# CrowPanel_Pico_Display-3_5_V1_0-240412.net
KiCad netlist of a schematic drawn in EAGLE
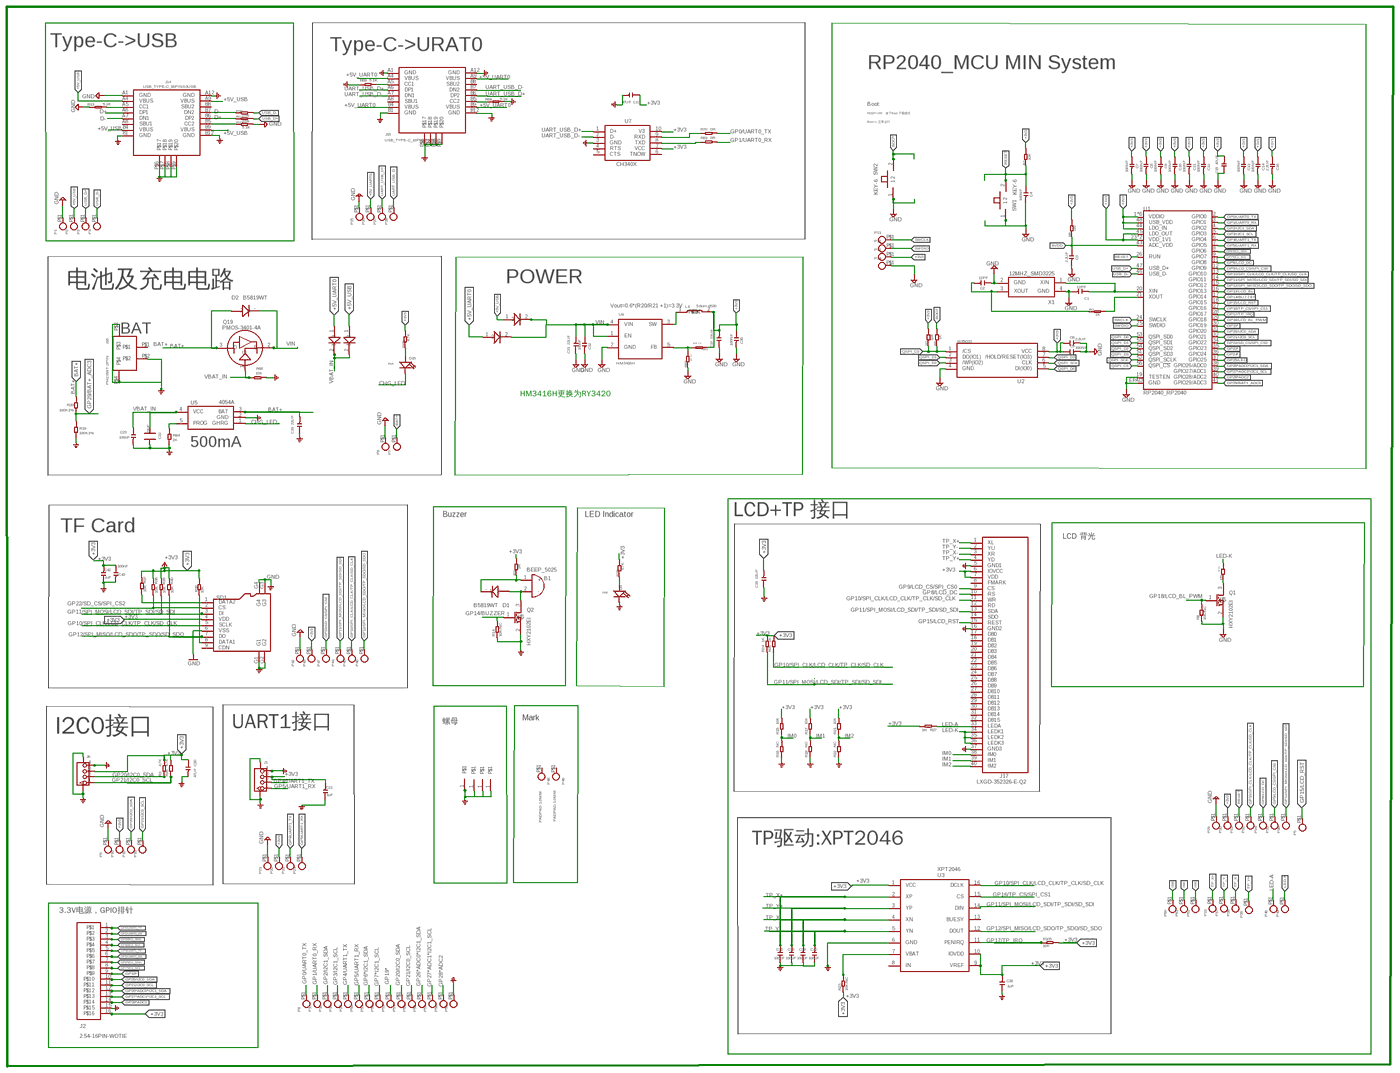
[diagram p0: schematic, sheet 1, overview]
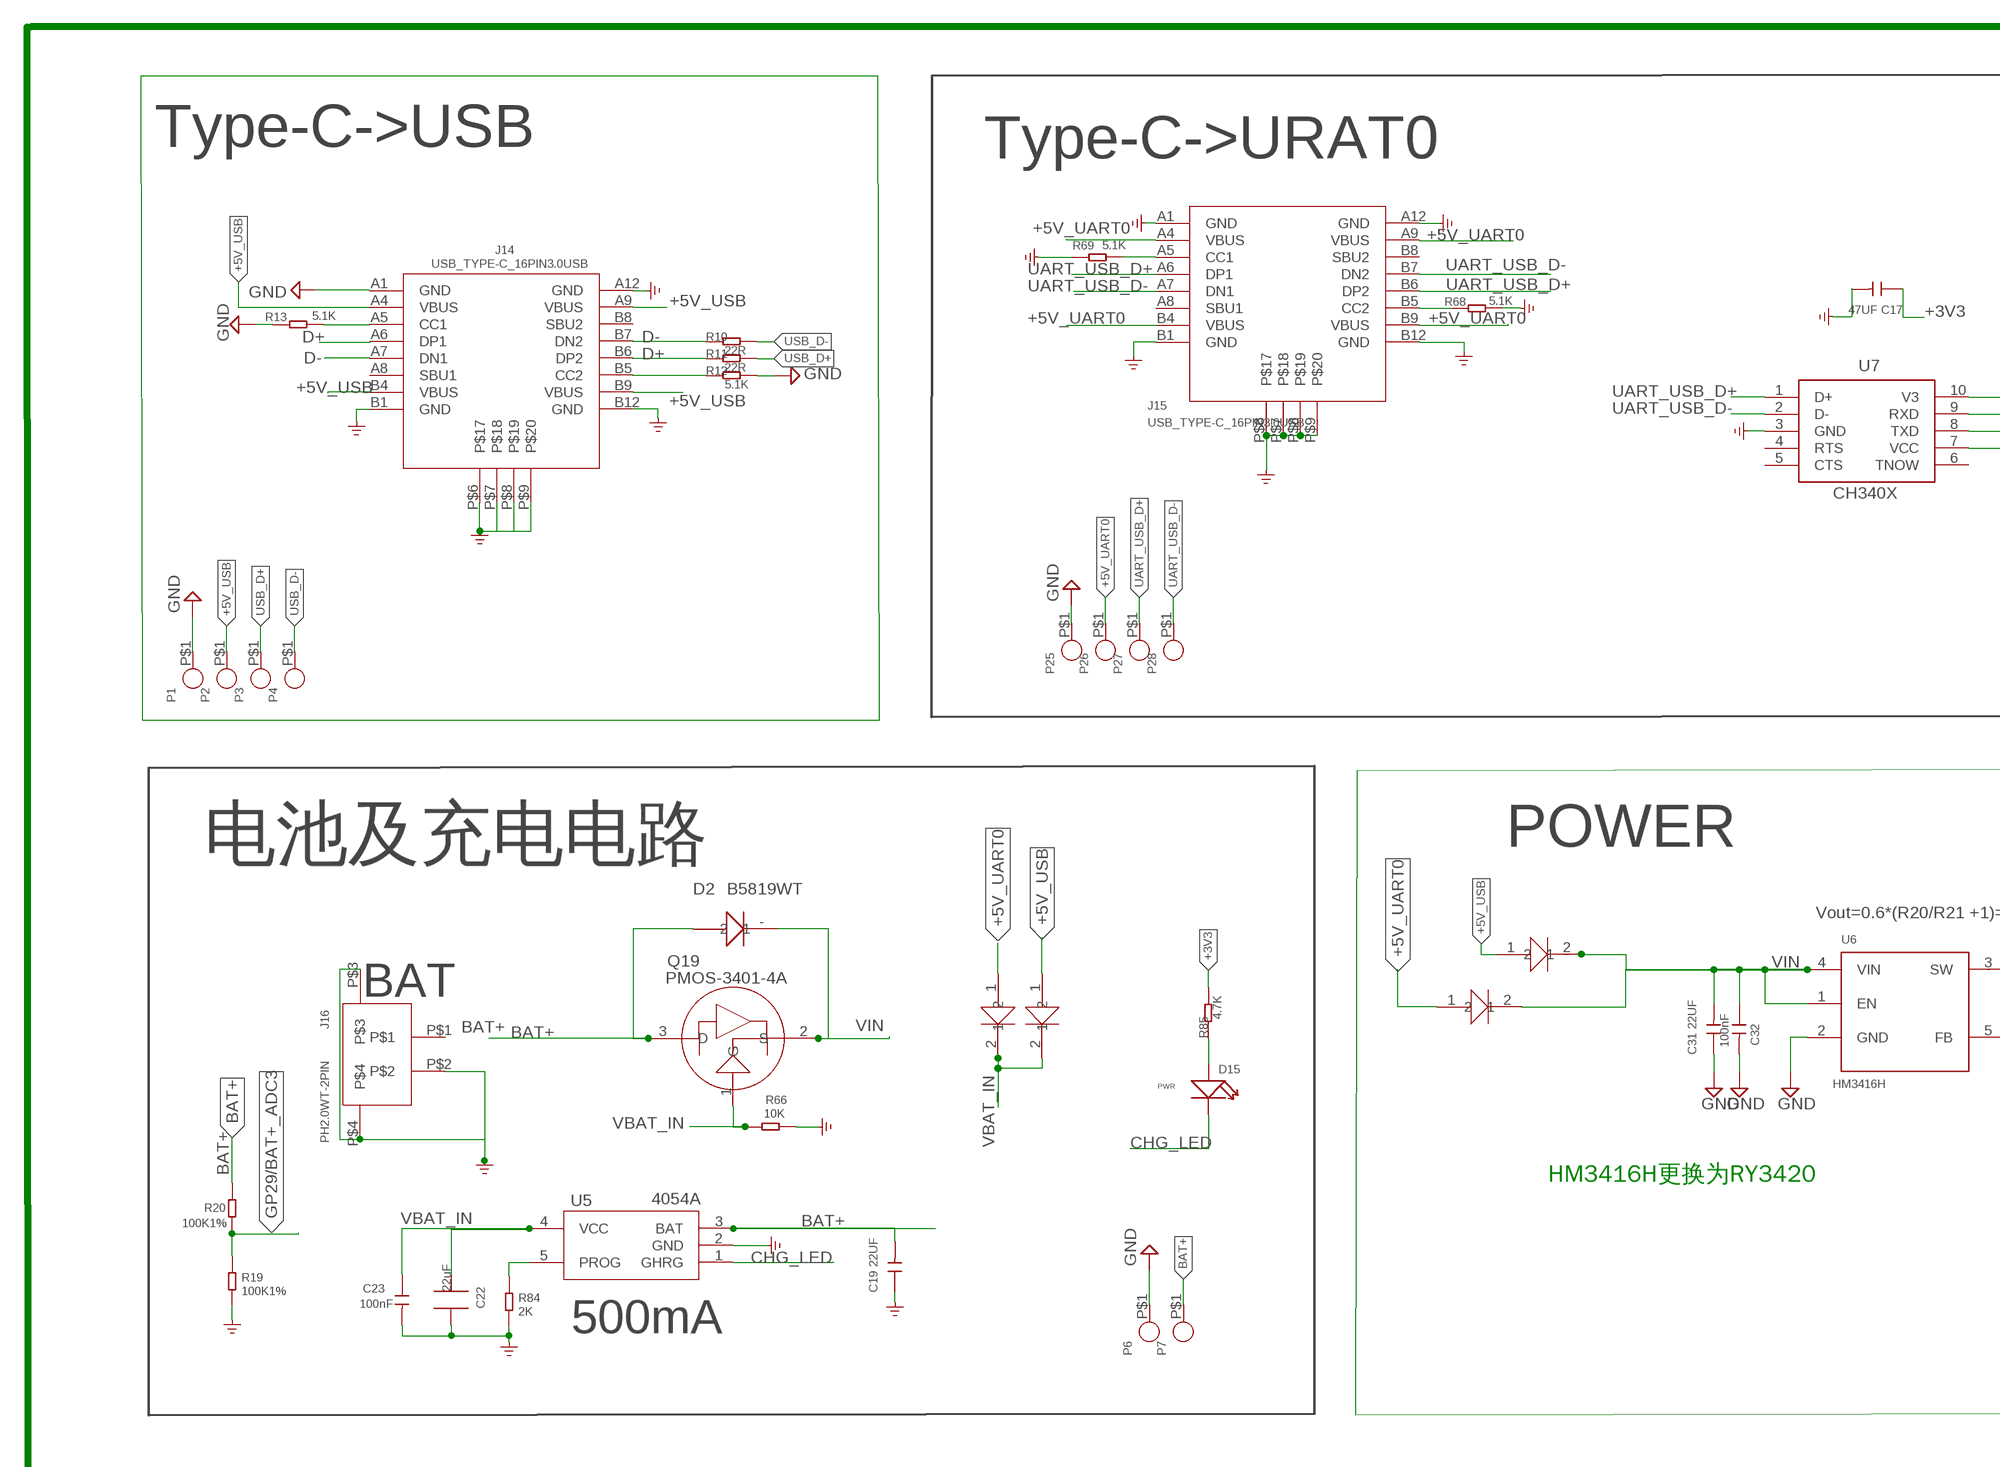
[diagram p1: schematic, sheet 1, part 1 of 4]
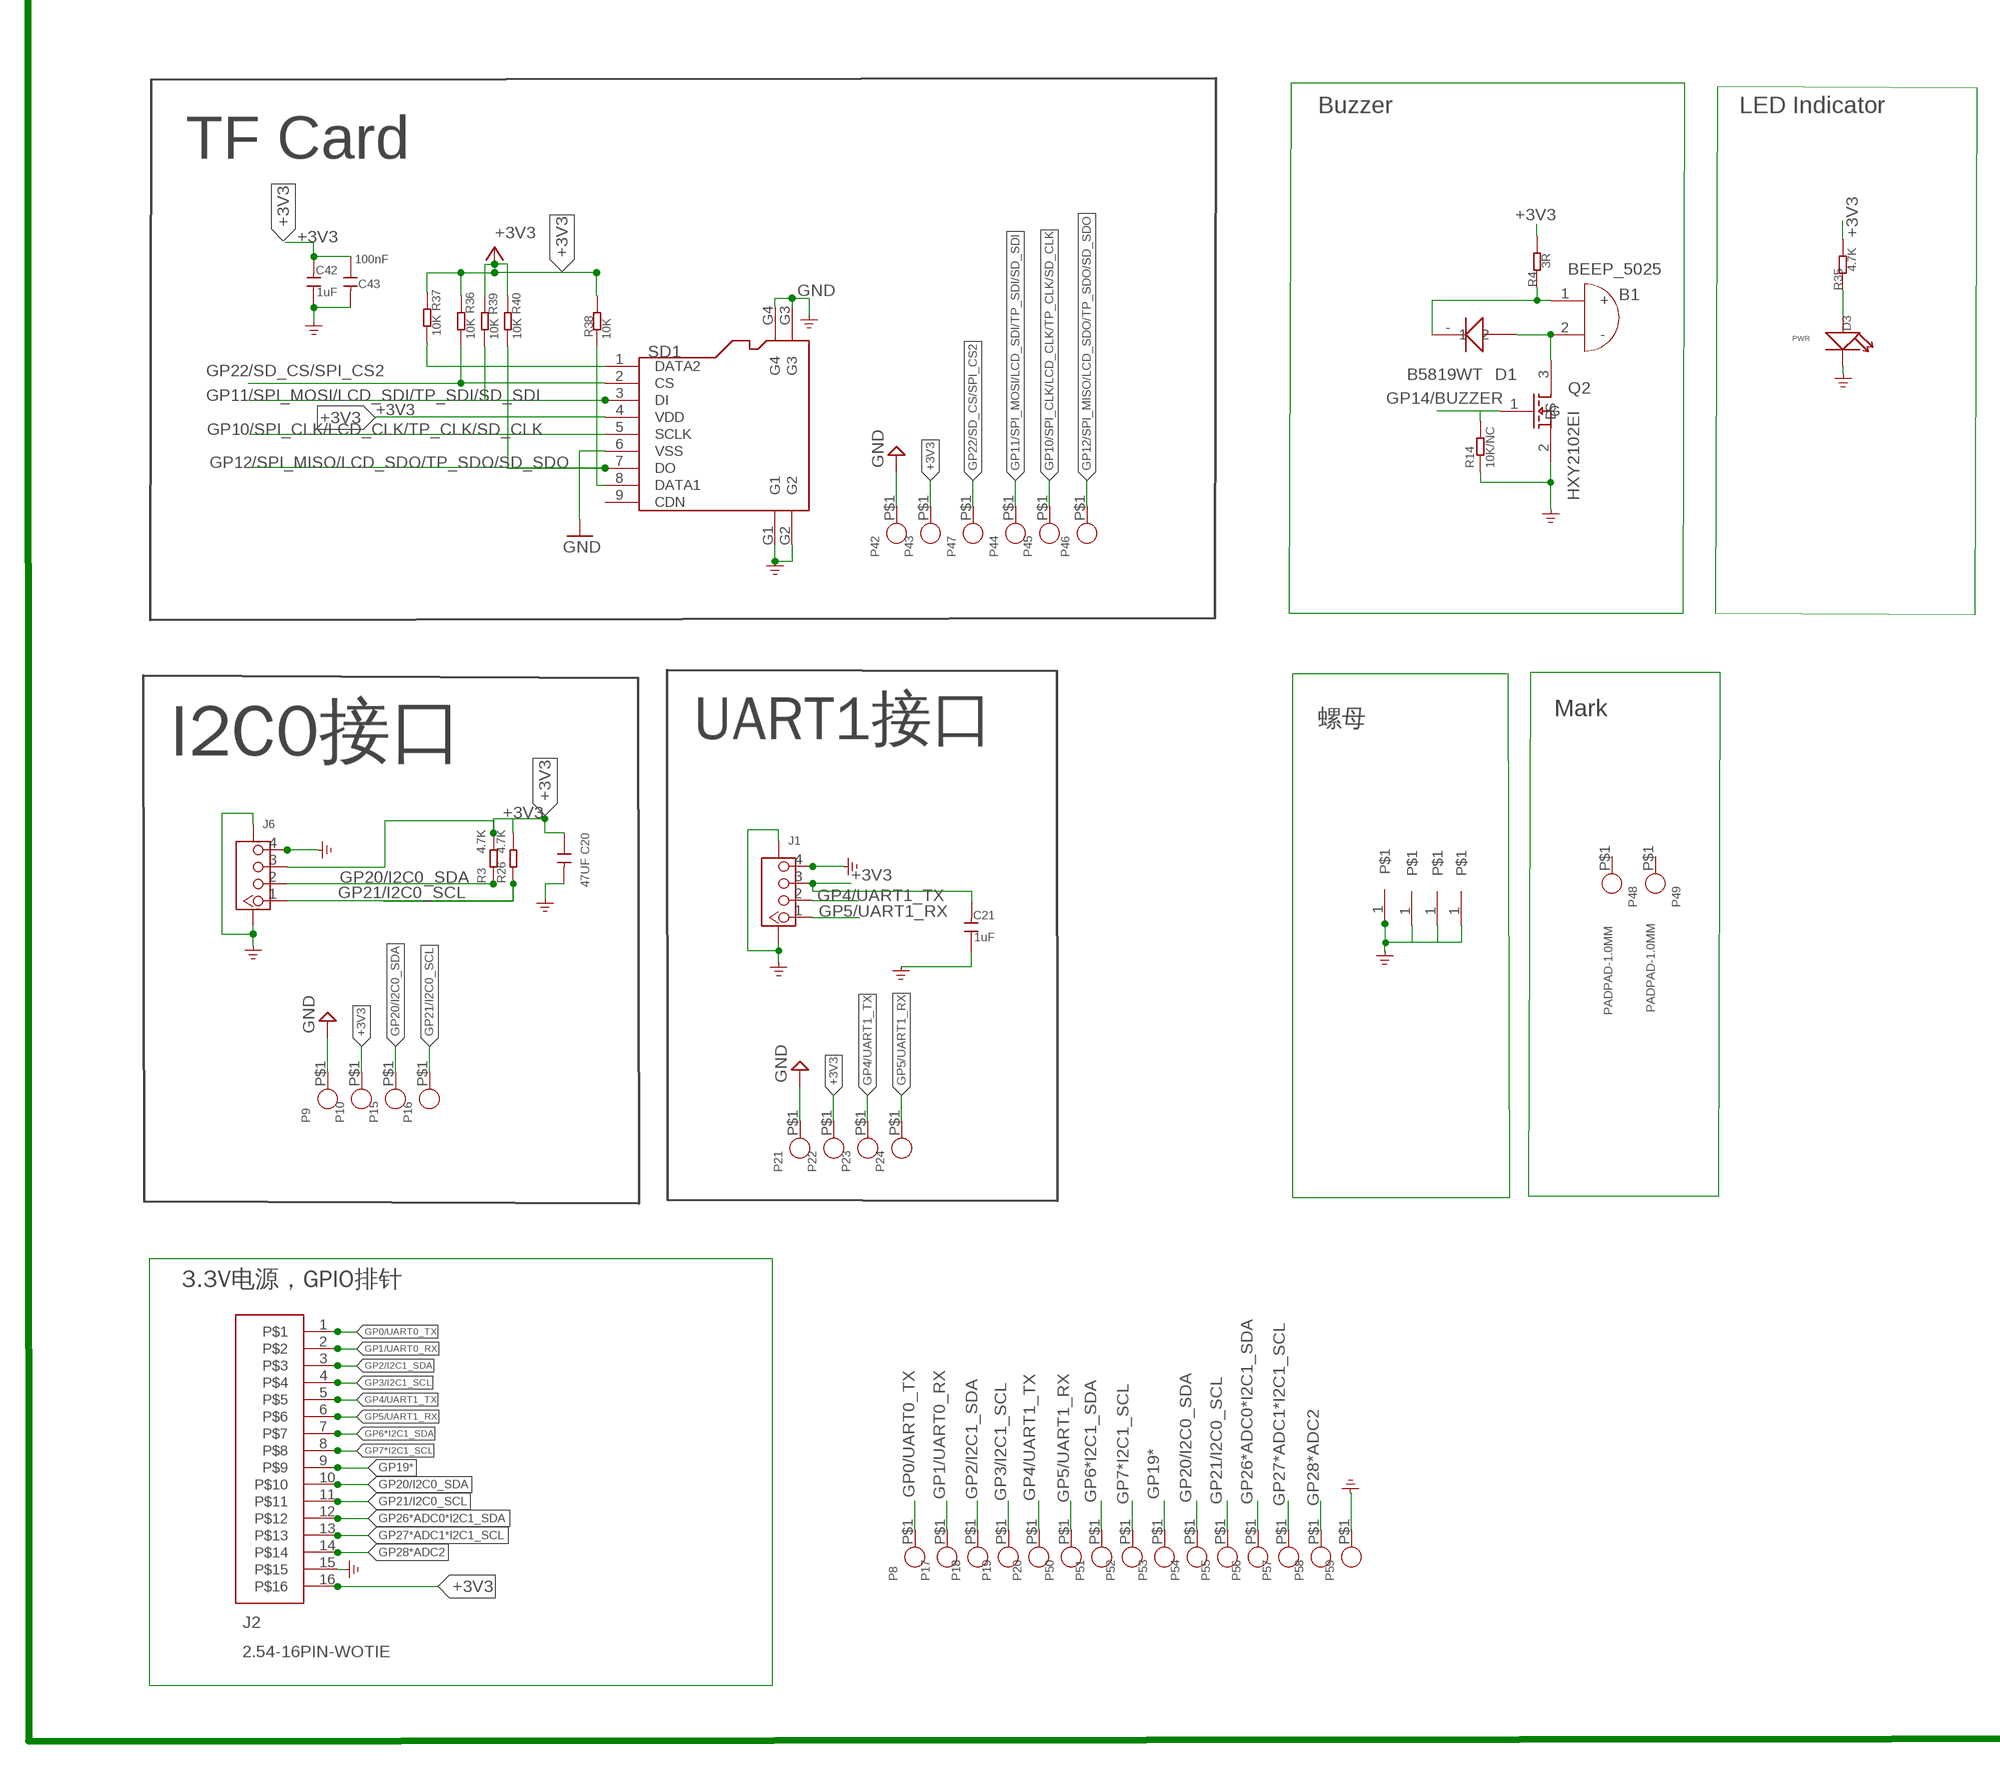
[diagram p2: schematic, sheet 1, part 2 of 4]
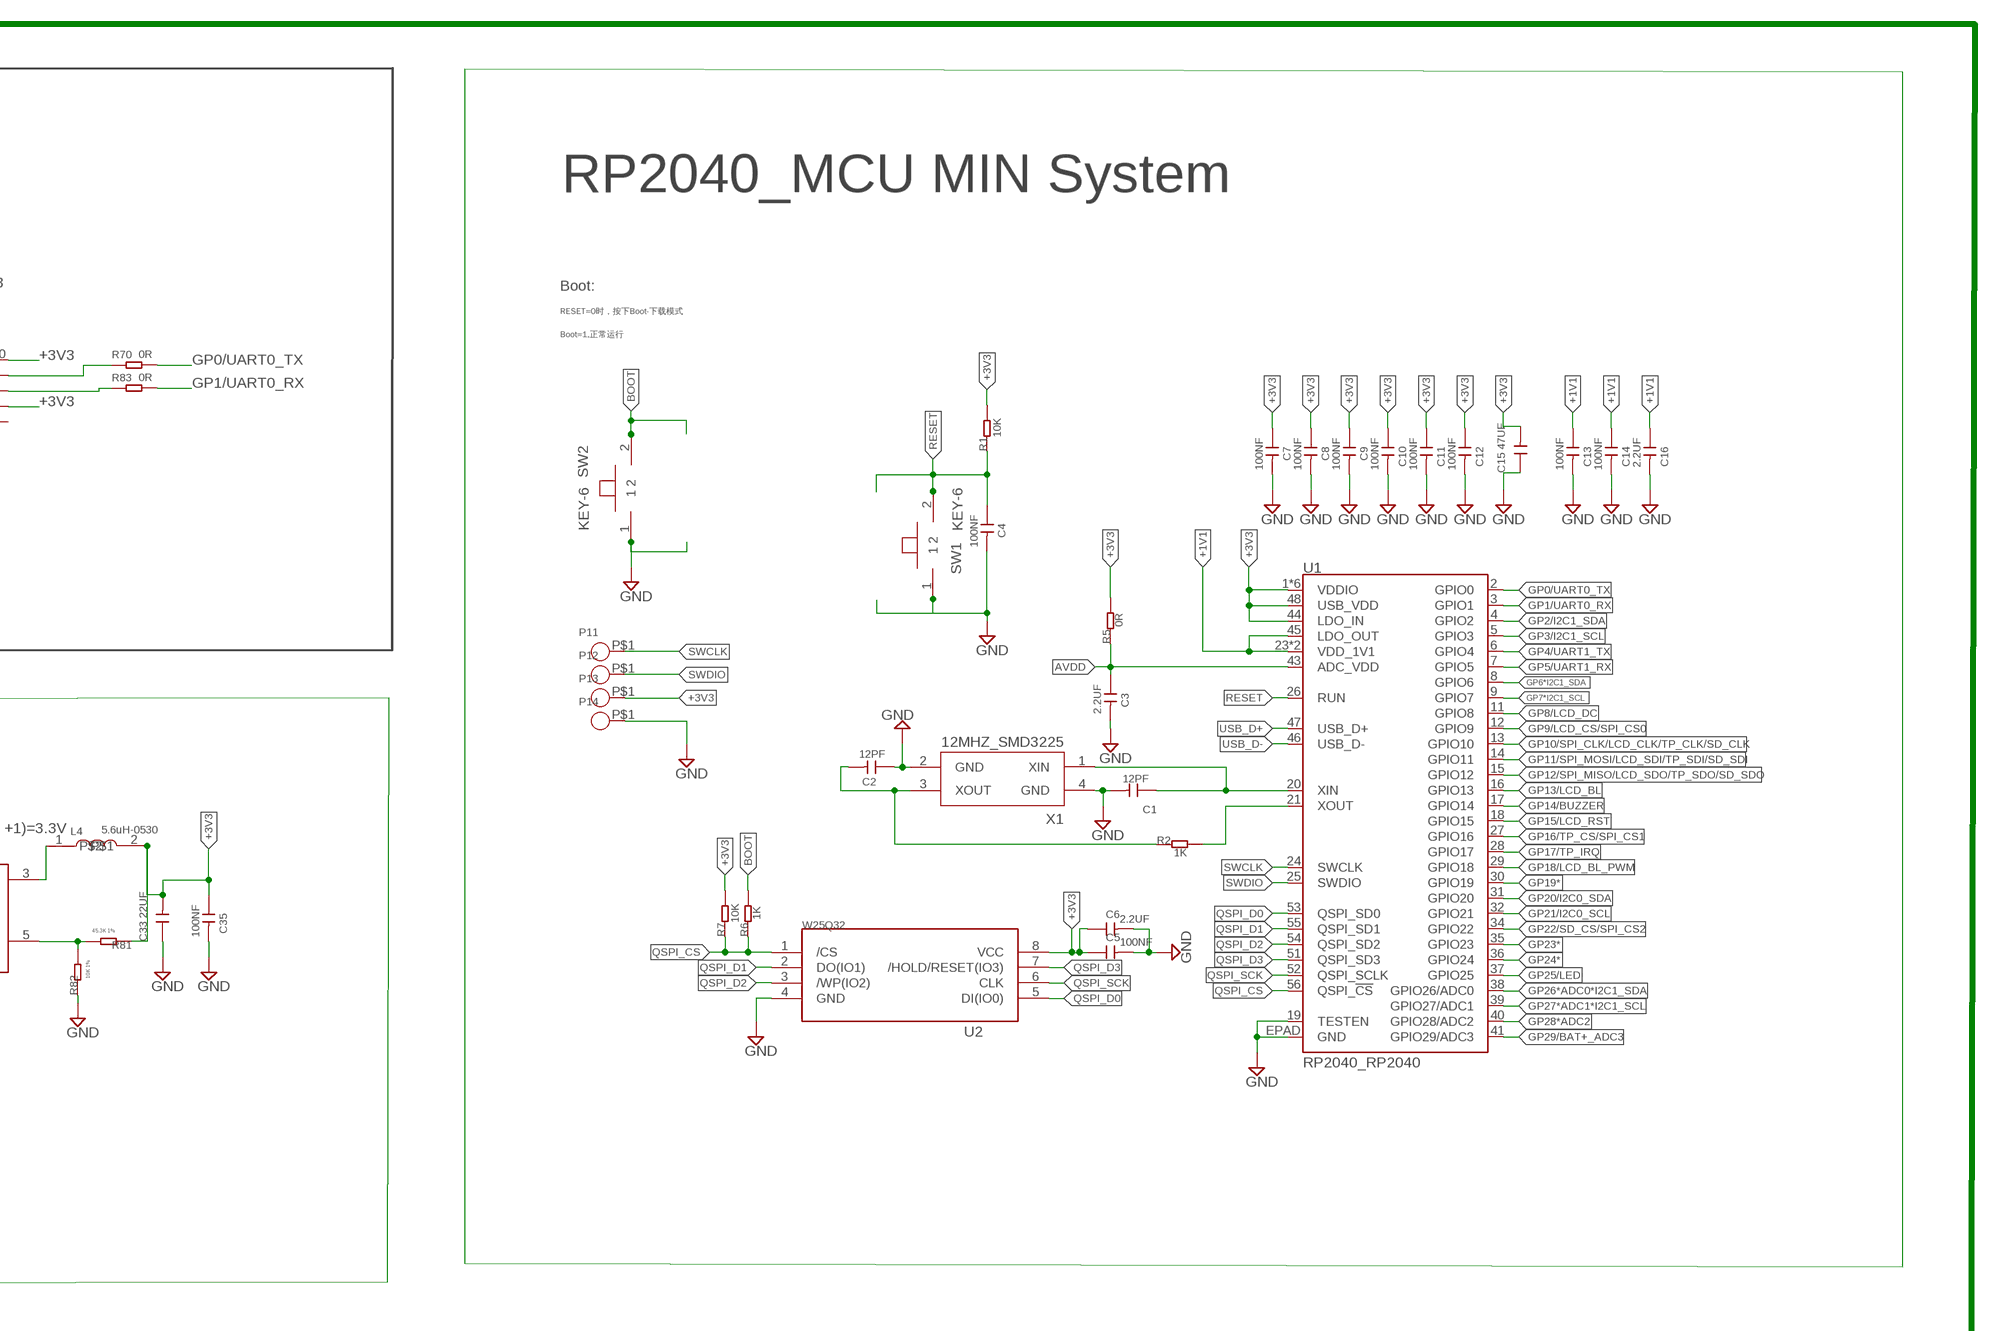
[diagram p3: schematic, sheet 1, part 3 of 4]
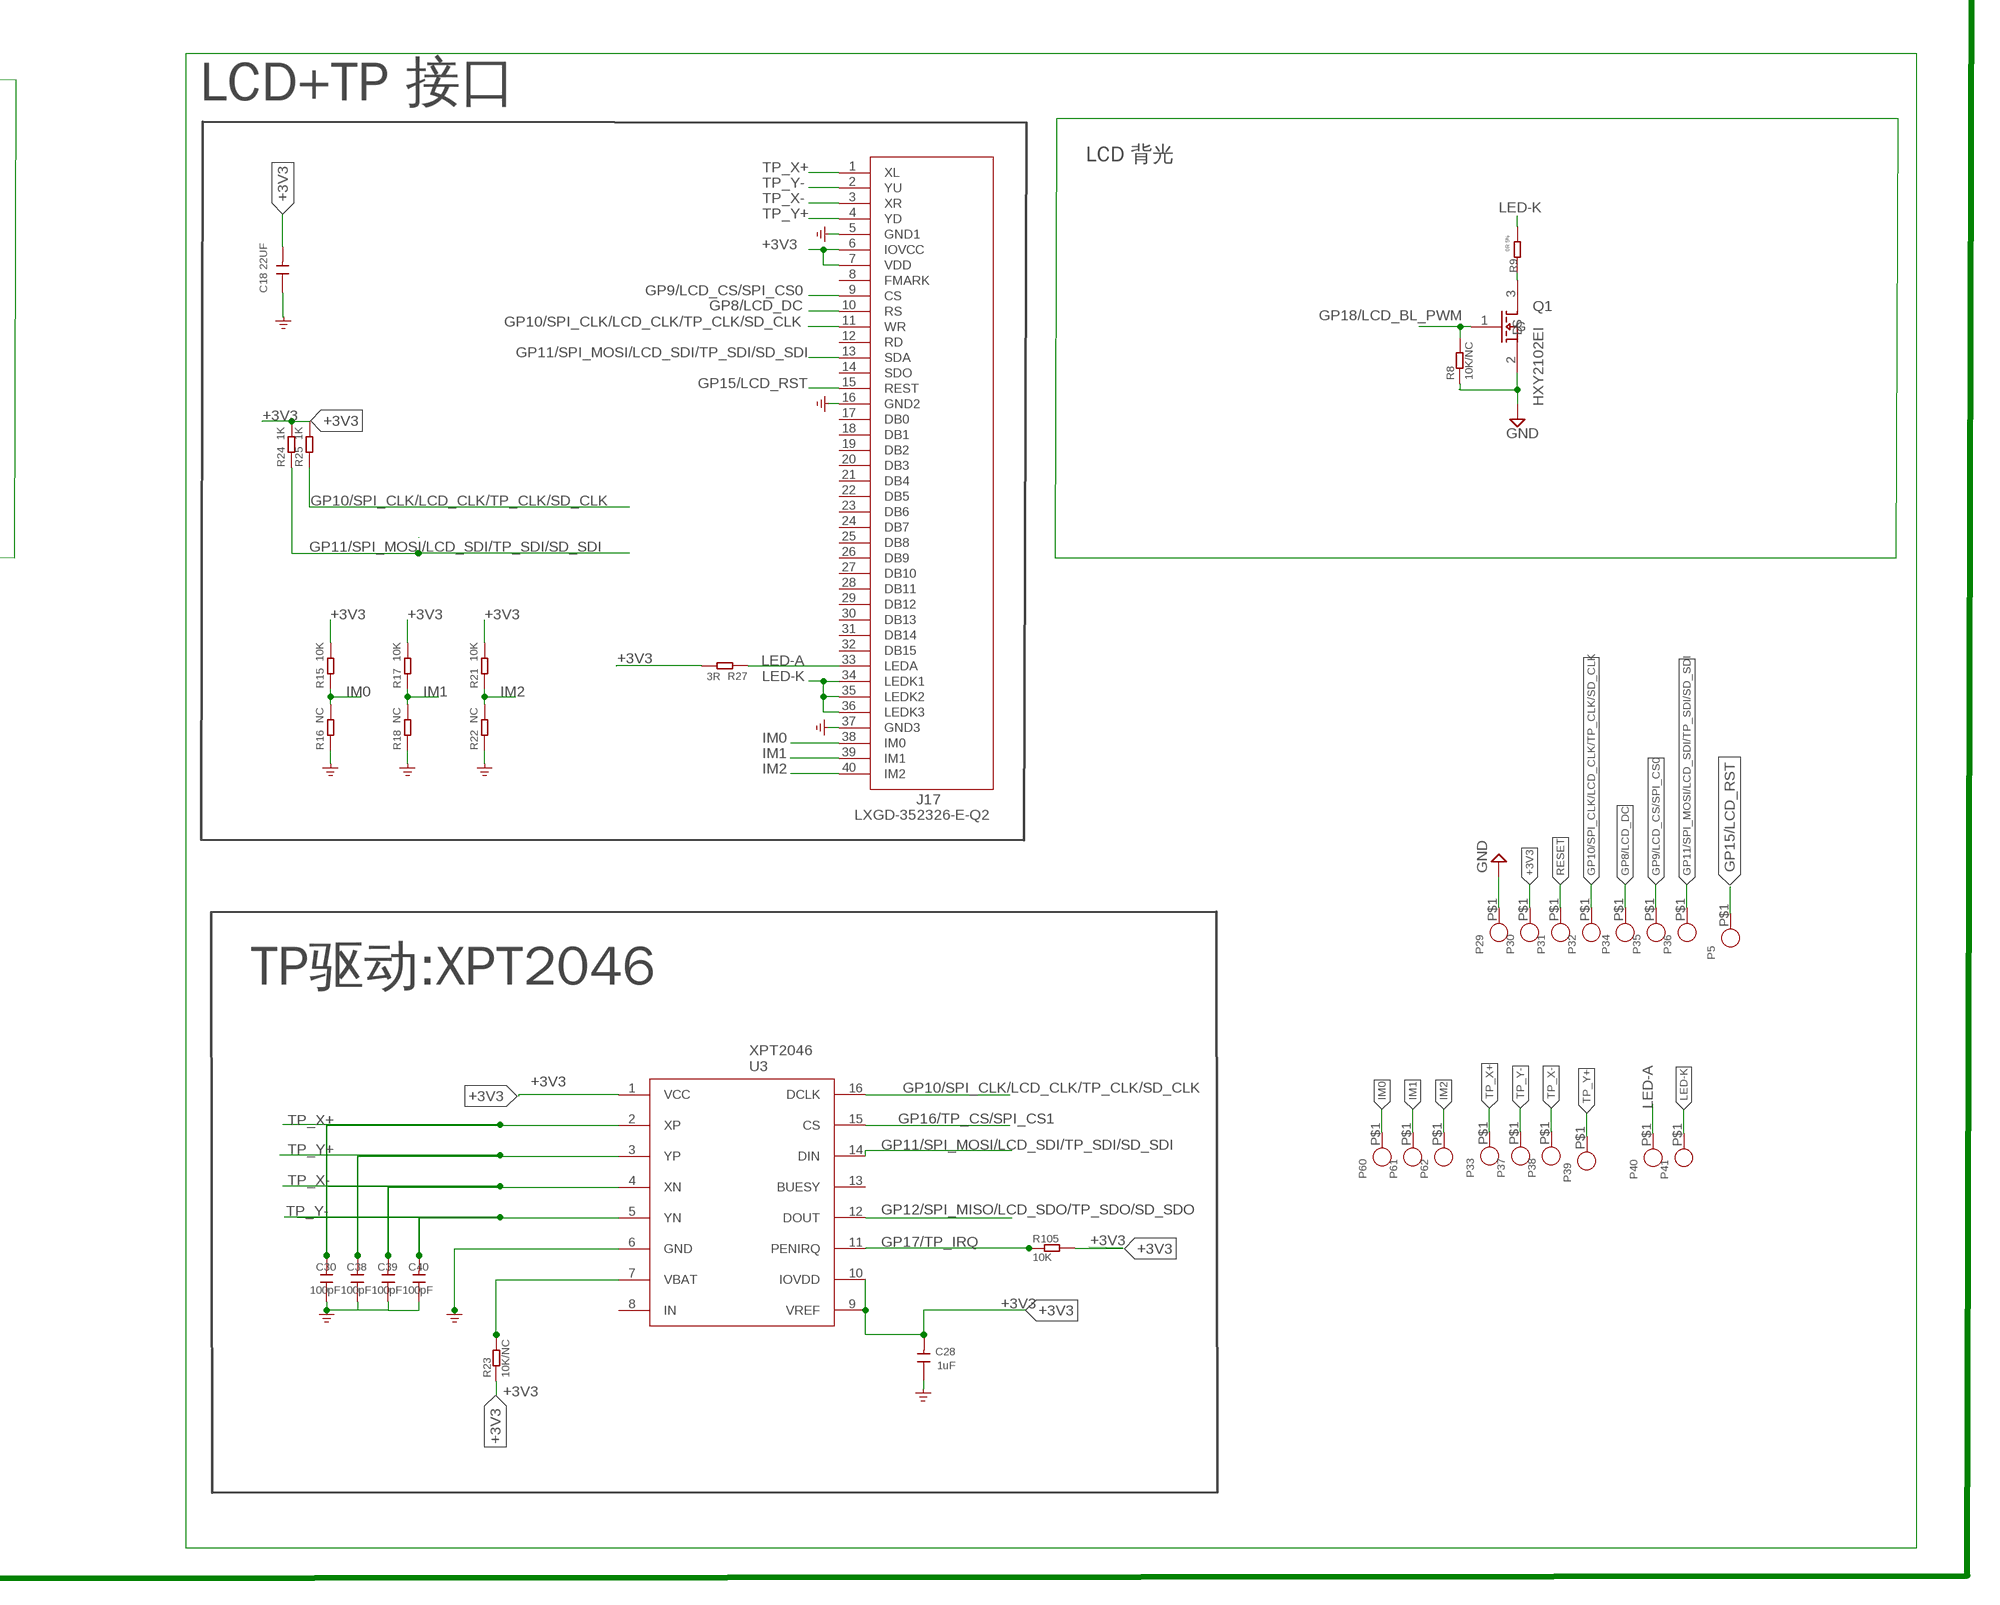
[diagram p4: schematic, sheet 1, part 4 of 4]

(export (version "E")
  (design (tool "Eeschema 10.0.6"))
  (components
    (comp (ref "B1")
      (value "BEEP_5025")
      (footprint "eagle-import:BEEP_5025")
      (libsource (lib "eagle-import") (part "BEEP_5025"))
    )
    (comp (ref "C1")
      (value "12PF")
      (footprint "eagle-import:A_XBJ_0603")
      (libsource (lib "eagle-import") (part "A_XBJ_C0603"))
    )
    (comp (ref "C2")
      (value "12PF")
      (footprint "eagle-import:A_XBJ_0603")
      (libsource (lib "eagle-import") (part "A_XBJ_C0603"))
    )
    (comp (ref "C3")
      (value "2.2UF")
      (footprint "eagle-import:A_XBJ_0603")
      (libsource (lib "eagle-import") (part "A_XBJ_C0603"))
    )
    (comp (ref "C4")
      (value "100NF")
      (footprint "eagle-import:A_XBJ_0603")
      (libsource (lib "eagle-import") (part "A_XBJ_C0603"))
    )
    (comp (ref "C5")
      (value "100NF")
      (footprint "eagle-import:A_XBJ_0603")
      (libsource (lib "eagle-import") (part "A_XBJ_C0603"))
    )
    (comp (ref "C6")
      (value "2.2UF")
      (footprint "eagle-import:A_XBJ_0603")
      (libsource (lib "eagle-import") (part "A_XBJ_C0603"))
    )
    (comp (ref "C7")
      (value "100NF")
      (footprint "eagle-import:A_XBJ_0603")
      (libsource (lib "eagle-import") (part "A_XBJ_C0603"))
    )
    (comp (ref "C8")
      (value "100NF")
      (footprint "eagle-import:A_XBJ_0603")
      (libsource (lib "eagle-import") (part "A_XBJ_C0603"))
    )
    (comp (ref "C9")
      (value "100NF")
      (footprint "eagle-import:A_XBJ_0603")
      (libsource (lib "eagle-import") (part "A_XBJ_C0603"))
    )
    (comp (ref "C10")
      (value "100NF")
      (footprint "eagle-import:A_XBJ_0603")
      (libsource (lib "eagle-import") (part "A_XBJ_C0603"))
    )
    (comp (ref "C11")
      (value "100NF")
      (footprint "eagle-import:A_XBJ_0603")
      (libsource (lib "eagle-import") (part "A_XBJ_C0603"))
    )
    (comp (ref "C12")
      (value "100NF")
      (footprint "eagle-import:A_XBJ_0603")
      (libsource (lib "eagle-import") (part "A_XBJ_C0603"))
    )
    (comp (ref "C13")
      (value "100NF")
      (footprint "eagle-import:A_XBJ_0603")
      (libsource (lib "eagle-import") (part "A_XBJ_C0603"))
    )
    (comp (ref "C14")
      (value "100NF")
      (footprint "eagle-import:A_XBJ_0603")
      (libsource (lib "eagle-import") (part "A_XBJ_C0603"))
    )
    (comp (ref "C15")
      (value "47UF")
      (footprint "eagle-import:A_XBJ_0805")
      (libsource (lib "eagle-import") (part "A_XBJ_C0805"))
    )
    (comp (ref "C16")
      (value "2.2UF")
      (footprint "eagle-import:A_XBJ_0603")
      (libsource (lib "eagle-import") (part "A_XBJ_C0603"))
    )
    (comp (ref "C17")
      (value "47UF")
      (footprint "eagle-import:A_XBJ_0805")
      (libsource (lib "eagle-import") (part "A_XBJ_C0805"))
    )
    (comp (ref "C18")
      (value "22UF")
      (footprint "eagle-import:A_XBJ_0805")
      (libsource (lib "eagle-import") (part "A_XBJ_C0805"))
    )
    (comp (ref "C19")
      (value "22UF")
      (footprint "eagle-import:A_XBJ_0805")
      (libsource (lib "eagle-import") (part "A_XBJ_C0805"))
    )
    (comp (ref "C20")
      (value "47UF")
      (footprint "eagle-import:A_XBJ_0805")
      (libsource (lib "eagle-import") (part "A_XBJ_C0805"))
    )
    (comp (ref "C21")
      (value "1uF")
      (footprint "eagle-import:DISCRETE_C0603")
      (libsource (lib "eagle-import") (part "DISCRETE_C-0603"))
    )
    (comp (ref "C22")
      (value "22uF")
      (footprint "eagle-import:0805_S")
      (libsource (lib "eagle-import") (part "C0805_S"))
    )
    (comp (ref "C23")
      (value "100nF")
      (footprint "eagle-import:C0603")
      (libsource (lib "eagle-import") (part "C-0603"))
    )
    (comp (ref "C28")
      (value "1uF")
      (footprint "eagle-import:DISCRETE_C0603")
      (libsource (lib "eagle-import") (part "DISCRETE_C-0603"))
    )
    (comp (ref "C30")
      (value "100pF")
      (footprint "eagle-import:0603")
      (libsource (lib "eagle-import") (part "C0603"))
    )
    (comp (ref "C31")
      (value "22UF")
      (footprint "eagle-import:A_XBJ_0805")
      (libsource (lib "eagle-import") (part "A_XBJ_C0805"))
    )
    (comp (ref "C32")
      (value "100nF")
      (footprint "eagle-import:A_XBJ_0603")
      (libsource (lib "eagle-import") (part "A_XBJ_C0603"))
    )
    (comp (ref "C33")
      (value "22UF")
      (footprint "eagle-import:A_XBJ_0805")
      (libsource (lib "eagle-import") (part "A_XBJ_C0805"))
    )
    (comp (ref "C35")
      (value "100NF")
      (footprint "eagle-import:A_XBJ_0603")
      (libsource (lib "eagle-import") (part "A_XBJ_C0603"))
    )
    (comp (ref "C38")
      (value "100pF")
      (footprint "eagle-import:0603")
      (libsource (lib "eagle-import") (part "C0603"))
    )
    (comp (ref "C39")
      (value "100pF")
      (footprint "eagle-import:0603")
      (libsource (lib "eagle-import") (part "C0603"))
    )
    (comp (ref "C40")
      (value "100pF")
      (footprint "eagle-import:0603")
      (libsource (lib "eagle-import") (part "C0603"))
    )
    (comp (ref "C42")
      (value "1uF")
      (footprint "eagle-import:DISCRETE_C0603")
      (libsource (lib "eagle-import") (part "DISCRETE_C-0603"))
    )
    (comp (ref "C43")
      (value "100nF")
      (footprint "eagle-import:C0603")
      (libsource (lib "eagle-import") (part "C-0603"))
    )
    (comp (ref "D1")
      (value "B5819WT")
      (footprint "eagle-import:SOD-523")
      (libsource (lib "eagle-import") (part "DIODE_W"))
    )
    (comp (ref "D2")
      (value "B5819WT")
      (footprint "eagle-import:SOD-523")
      (libsource (lib "eagle-import") (part "DIODE_W"))
    )
    (comp (ref "D3")
      (value "DISCRETE_007-LED0603")
      (footprint "eagle-import:DISCRETE_D0603")
      (libsource (lib "eagle-import") (part "DISCRETE_007-LED0603"))
    )
    (comp (ref "D4")
      (value "SOD-323")
      (footprint "eagle-import:SOD-323")
      (libsource (lib "eagle-import") (part "SOD-323"))
    )
    (comp (ref "D5")
      (value "SOD-323")
      (footprint "eagle-import:SOD-323")
      (libsource (lib "eagle-import") (part "SOD-323"))
    )
    (comp (ref "D6")
      (value "SOD-323")
      (footprint "eagle-import:SOD-323")
      (libsource (lib "eagle-import") (part "SOD-323"))
    )
    (comp (ref "D8")
      (value "SOD-323")
      (footprint "eagle-import:SOD-323")
      (libsource (lib "eagle-import") (part "SOD-323"))
    )
    (comp (ref "D15")
      (value "DISCRETE_007-LED0603")
      (footprint "eagle-import:DISCRETE_D0603")
      (libsource (lib "eagle-import") (part "DISCRETE_007-LED0603"))
    )
    (comp (ref "J1")
      (value "CONNECTOR_TWIG-4P-2.0-SMD-FEMALE-REINFORCE90D")
      (footprint "eagle-import:CONNECTOR_4P-SMD-2.0-90D")
      (libsource (lib "eagle-import") (part "CONNECTOR_TWIG-4P-2.0-SMD-FEMALE-REINFORCE90D"))
    )
    (comp (ref "J2")
      (value "2.54-16PIN-WOTIE")
      (footprint "eagle-import:2.54-16P-WOTIE")
      (libsource (lib "eagle-import") (part "2.54-16PIN-WOTIE"))
    )
    (comp (ref "J6")
      (value "CONNECTOR_TWIG-4P-2.0-SMD-FEMALE-REINFORCE90D")
      (footprint "eagle-import:CONNECTOR_4P-SMD-2.0-90D")
      (libsource (lib "eagle-import") (part "CONNECTOR_TWIG-4P-2.0-SMD-FEMALE-REINFORCE90D"))
    )
    (comp (ref "J14")
      (value "USB_TYPE-C_16PIN3.0USB")
      (footprint "eagle-import:KEVIN_3.0TYPEC-SMD")
      (libsource (lib "eagle-import") (part "USB_TYPE-C_16PIN3.0USB"))
    )
    (comp (ref "J15")
      (value "USB_TYPE-C_16PIN3.0USB")
      (footprint "eagle-import:KEVIN_3.0TYPEC-SMD")
      (libsource (lib "eagle-import") (part "USB_TYPE-C_16PIN3.0USB"))
    )
    (comp (ref "J16")
      (value "PH2.0WT-2PIN")
      (footprint "eagle-import:PH2.0WT-2PIN")
      (libsource (lib "eagle-import") (part "PH2.0WT-2PIN"))
    )
    (comp (ref "J17")
      (value "LXGD-352326-E-Q2")
      (footprint "eagle-import:40PIN-0.5MM")
      (libsource (lib "eagle-import") (part "LXGD-28A1044-E-T2"))
    )
    (comp (ref "L4")
      (value "5.6uH-0530")
      (footprint "eagle-import:CD54_CD54")
      (libsource (lib "eagle-import") (part "L-0530"))
    )
    (comp (ref "P1")
      (value "CROWPI_POW_PADPAD-1.0MM")
      (footprint "eagle-import:CROWPI_POW_PAD-1.0MM")
      (libsource (lib "eagle-import") (part "CROWPI_POW_PADPAD-1.0MM"))
    )
    (comp (ref "P2")
      (value "CROWPI_POW_PADPAD-1.0MM")
      (footprint "eagle-import:CROWPI_POW_PAD-1.0MM")
      (libsource (lib "eagle-import") (part "CROWPI_POW_PADPAD-1.0MM"))
    )
    (comp (ref "P3")
      (value "CROWPI_POW_PADPAD-1.0MM")
      (footprint "eagle-import:CROWPI_POW_PAD-1.0MM")
      (libsource (lib "eagle-import") (part "CROWPI_POW_PADPAD-1.0MM"))
    )
    (comp (ref "P4")
      (value "CROWPI_POW_PADPAD-1.0MM")
      (footprint "eagle-import:CROWPI_POW_PAD-1.0MM")
      (libsource (lib "eagle-import") (part "CROWPI_POW_PADPAD-1.0MM"))
    )
    (comp (ref "P5")
      (value "CROWPI_POW_PADPAD-1.0MM")
      (footprint "eagle-import:CROWPI_POW_PAD-1.0MM")
      (libsource (lib "eagle-import") (part "CROWPI_POW_PADPAD-1.0MM"))
    )
    (comp (ref "P6")
      (value "CROWPI_POW_PADPAD-1.0MM")
      (footprint "eagle-import:CROWPI_POW_PAD-1.0MM")
      (libsource (lib "eagle-import") (part "CROWPI_POW_PADPAD-1.0MM"))
    )
    (comp (ref "P7")
      (value "CROWPI_POW_PADPAD-1.0MM")
      (footprint "eagle-import:CROWPI_POW_PAD-1.0MM")
      (libsource (lib "eagle-import") (part "CROWPI_POW_PADPAD-1.0MM"))
    )
    (comp (ref "P8")
      (value "CROWPI_POW_PADPAD-1.0MM")
      (footprint "eagle-import:CROWPI_POW_PAD-1.0MM")
      (libsource (lib "eagle-import") (part "CROWPI_POW_PADPAD-1.0MM"))
    )
    (comp (ref "P9")
      (value "CROWPI_POW_PADPAD-1.0MM")
      (footprint "eagle-import:CROWPI_POW_PAD-1.0MM")
      (libsource (lib "eagle-import") (part "CROWPI_POW_PADPAD-1.0MM"))
    )
    (comp (ref "P10")
      (value "CROWPI_POW_PADPAD-1.0MM")
      (footprint "eagle-import:CROWPI_POW_PAD-1.0MM")
      (libsource (lib "eagle-import") (part "CROWPI_POW_PADPAD-1.0MM"))
    )
    (comp (ref "P11")
      (value "CROWPI_POW_PADPAD-1.0MM")
      (footprint "eagle-import:CROWPI_POW_PAD-1.0MM")
      (libsource (lib "eagle-import") (part "CROWPI_POW_PADPAD-1.0MM"))
    )
    (comp (ref "P12")
      (value "CROWPI_POW_PADPAD-1.0MM")
      (footprint "eagle-import:CROWPI_POW_PAD-1.0MM")
      (libsource (lib "eagle-import") (part "CROWPI_POW_PADPAD-1.0MM"))
    )
    (comp (ref "P13")
      (value "CROWPI_POW_PADPAD-1.0MM")
      (footprint "eagle-import:CROWPI_POW_PAD-1.0MM")
      (libsource (lib "eagle-import") (part "CROWPI_POW_PADPAD-1.0MM"))
    )
    (comp (ref "P14")
      (value "CROWPI_POW_PADPAD-1.0MM")
      (footprint "eagle-import:CROWPI_POW_PAD-1.0MM")
      (libsource (lib "eagle-import") (part "CROWPI_POW_PADPAD-1.0MM"))
    )
    (comp (ref "P15")
      (value "CROWPI_POW_PADPAD-1.0MM")
      (footprint "eagle-import:CROWPI_POW_PAD-1.0MM")
      (libsource (lib "eagle-import") (part "CROWPI_POW_PADPAD-1.0MM"))
    )
    (comp (ref "P16")
      (value "CROWPI_POW_PADPAD-1.0MM")
      (footprint "eagle-import:CROWPI_POW_PAD-1.0MM")
      (libsource (lib "eagle-import") (part "CROWPI_POW_PADPAD-1.0MM"))
    )
    (comp (ref "P17")
      (value "CROWPI_POW_PADPAD-1.0MM")
      (footprint "eagle-import:CROWPI_POW_PAD-1.0MM")
      (libsource (lib "eagle-import") (part "CROWPI_POW_PADPAD-1.0MM"))
    )
    (comp (ref "P18")
      (value "CROWPI_POW_PADPAD-1.0MM")
      (footprint "eagle-import:CROWPI_POW_PAD-1.0MM")
      (libsource (lib "eagle-import") (part "CROWPI_POW_PADPAD-1.0MM"))
    )
    (comp (ref "P19")
      (value "CROWPI_POW_PADPAD-1.0MM")
      (footprint "eagle-import:CROWPI_POW_PAD-1.0MM")
      (libsource (lib "eagle-import") (part "CROWPI_POW_PADPAD-1.0MM"))
    )
    (comp (ref "P20")
      (value "CROWPI_POW_PADPAD-1.0MM")
      (footprint "eagle-import:CROWPI_POW_PAD-1.0MM")
      (libsource (lib "eagle-import") (part "CROWPI_POW_PADPAD-1.0MM"))
    )
    (comp (ref "P21")
      (value "CROWPI_POW_PADPAD-1.0MM")
      (footprint "eagle-import:CROWPI_POW_PAD-1.0MM")
      (libsource (lib "eagle-import") (part "CROWPI_POW_PADPAD-1.0MM"))
    )
    (comp (ref "P22")
      (value "CROWPI_POW_PADPAD-1.0MM")
      (footprint "eagle-import:CROWPI_POW_PAD-1.0MM")
      (libsource (lib "eagle-import") (part "CROWPI_POW_PADPAD-1.0MM"))
    )
    (comp (ref "P23")
      (value "CROWPI_POW_PADPAD-1.0MM")
      (footprint "eagle-import:CROWPI_POW_PAD-1.0MM")
      (libsource (lib "eagle-import") (part "CROWPI_POW_PADPAD-1.0MM"))
    )
    (comp (ref "P24")
      (value "CROWPI_POW_PADPAD-1.0MM")
      (footprint "eagle-import:CROWPI_POW_PAD-1.0MM")
      (libsource (lib "eagle-import") (part "CROWPI_POW_PADPAD-1.0MM"))
    )
    (comp (ref "P25")
      (value "CROWPI_POW_PADPAD-1.0MM")
      (footprint "eagle-import:CROWPI_POW_PAD-1.0MM")
      (libsource (lib "eagle-import") (part "CROWPI_POW_PADPAD-1.0MM"))
    )
    (comp (ref "P26")
      (value "CROWPI_POW_PADPAD-1.0MM")
      (footprint "eagle-import:CROWPI_POW_PAD-1.0MM")
      (libsource (lib "eagle-import") (part "CROWPI_POW_PADPAD-1.0MM"))
    )
    (comp (ref "P27")
      (value "CROWPI_POW_PADPAD-1.0MM")
      (footprint "eagle-import:CROWPI_POW_PAD-1.0MM")
      (libsource (lib "eagle-import") (part "CROWPI_POW_PADPAD-1.0MM"))
    )
    (comp (ref "P28")
      (value "CROWPI_POW_PADPAD-1.0MM")
      (footprint "eagle-import:CROWPI_POW_PAD-1.0MM")
      (libsource (lib "eagle-import") (part "CROWPI_POW_PADPAD-1.0MM"))
    )
    (comp (ref "P29")
      (value "CROWPI_POW_PADPAD-1.0MM")
      (footprint "eagle-import:CROWPI_POW_PAD-1.0MM")
      (libsource (lib "eagle-import") (part "CROWPI_POW_PADPAD-1.0MM"))
    )
    (comp (ref "P30")
      (value "CROWPI_POW_PADPAD-1.0MM")
      (footprint "eagle-import:CROWPI_POW_PAD-1.0MM")
      (libsource (lib "eagle-import") (part "CROWPI_POW_PADPAD-1.0MM"))
    )
    (comp (ref "P31")
      (value "CROWPI_POW_PADPAD-1.0MM")
      (footprint "eagle-import:CROWPI_POW_PAD-1.0MM")
      (libsource (lib "eagle-import") (part "CROWPI_POW_PADPAD-1.0MM"))
    )
    (comp (ref "P32")
      (value "CROWPI_POW_PADPAD-1.0MM")
      (footprint "eagle-import:CROWPI_POW_PAD-1.0MM")
      (libsource (lib "eagle-import") (part "CROWPI_POW_PADPAD-1.0MM"))
    )
    (comp (ref "P33")
      (value "CROWPI_POW_PADPAD-1.0MM")
      (footprint "eagle-import:CROWPI_POW_PAD-1.0MM")
      (libsource (lib "eagle-import") (part "CROWPI_POW_PADPAD-1.0MM"))
    )
    (comp (ref "P34")
      (value "CROWPI_POW_PADPAD-1.0MM")
      (footprint "eagle-import:CROWPI_POW_PAD-1.0MM")
      (libsource (lib "eagle-import") (part "CROWPI_POW_PADPAD-1.0MM"))
    )
    (comp (ref "P35")
      (value "CROWPI_POW_PADPAD-1.0MM")
      (footprint "eagle-import:CROWPI_POW_PAD-1.0MM")
      (libsource (lib "eagle-import") (part "CROWPI_POW_PADPAD-1.0MM"))
    )
    (comp (ref "P36")
      (value "CROWPI_POW_PADPAD-1.0MM")
      (footprint "eagle-import:CROWPI_POW_PAD-1.0MM")
      (libsource (lib "eagle-import") (part "CROWPI_POW_PADPAD-1.0MM"))
    )
    (comp (ref "P37")
      (value "CROWPI_POW_PADPAD-1.0MM")
      (footprint "eagle-import:CROWPI_POW_PAD-1.0MM")
      (libsource (lib "eagle-import") (part "CROWPI_POW_PADPAD-1.0MM"))
    )
    (comp (ref "P38")
      (value "CROWPI_POW_PADPAD-1.0MM")
      (footprint "eagle-import:CROWPI_POW_PAD-1.0MM")
      (libsource (lib "eagle-import") (part "CROWPI_POW_PADPAD-1.0MM"))
    )
    (comp (ref "P39")
      (value "CROWPI_POW_PADPAD-1.0MM")
      (footprint "eagle-import:CROWPI_POW_PAD-1.0MM")
      (libsource (lib "eagle-import") (part "CROWPI_POW_PADPAD-1.0MM"))
    )
    (comp (ref "P40")
      (value "CROWPI_POW_PADPAD-1.0MM")
      (footprint "eagle-import:CROWPI_POW_PAD-1.0MM")
      (libsource (lib "eagle-import") (part "CROWPI_POW_PADPAD-1.0MM"))
    )
    (comp (ref "P41")
      (value "CROWPI_POW_PADPAD-1.0MM")
      (footprint "eagle-import:CROWPI_POW_PAD-1.0MM")
      (libsource (lib "eagle-import") (part "CROWPI_POW_PADPAD-1.0MM"))
    )
    (comp (ref "P42")
      (value "CROWPI_POW_PADPAD-1.0MM")
      (footprint "eagle-import:CROWPI_POW_PAD-1.0MM")
      (libsource (lib "eagle-import") (part "CROWPI_POW_PADPAD-1.0MM"))
    )
    (comp (ref "P43")
      (value "CROWPI_POW_PADPAD-1.0MM")
      (footprint "eagle-import:CROWPI_POW_PAD-1.0MM")
      (libsource (lib "eagle-import") (part "CROWPI_POW_PADPAD-1.0MM"))
    )
    (comp (ref "P44")
      (value "CROWPI_POW_PADPAD-1.0MM")
      (footprint "eagle-import:CROWPI_POW_PAD-1.0MM")
      (libsource (lib "eagle-import") (part "CROWPI_POW_PADPAD-1.0MM"))
    )
    (comp (ref "P45")
      (value "CROWPI_POW_PADPAD-1.0MM")
      (footprint "eagle-import:CROWPI_POW_PAD-1.0MM")
      (libsource (lib "eagle-import") (part "CROWPI_POW_PADPAD-1.0MM"))
    )
    (comp (ref "P46")
      (value "CROWPI_POW_PADPAD-1.0MM")
      (footprint "eagle-import:CROWPI_POW_PAD-1.0MM")
      (libsource (lib "eagle-import") (part "CROWPI_POW_PADPAD-1.0MM"))
    )
    (comp (ref "P47")
      (value "CROWPI_POW_PADPAD-1.0MM")
      (footprint "eagle-import:CROWPI_POW_PAD-1.0MM")
      (libsource (lib "eagle-import") (part "CROWPI_POW_PADPAD-1.0MM"))
    )
    (comp (ref "P48")
      (value "PADPAD-1.0MM")
      (footprint "eagle-import:PAD-1.0MM")
      (libsource (lib "eagle-import") (part "PADPAD-1.0MM"))
    )
    (comp (ref "P49")
      (value "PADPAD-1.0MM")
      (footprint "eagle-import:PAD-1.0MM")
      (libsource (lib "eagle-import") (part "PADPAD-1.0MM"))
    )
    (comp (ref "P50")
      (value "CROWPI_POW_PADPAD-1.0MM")
      (footprint "eagle-import:CROWPI_POW_PAD-1.0MM")
      (libsource (lib "eagle-import") (part "CROWPI_POW_PADPAD-1.0MM"))
    )
    (comp (ref "P51")
      (value "CROWPI_POW_PADPAD-1.0MM")
      (footprint "eagle-import:CROWPI_POW_PAD-1.0MM")
      (libsource (lib "eagle-import") (part "CROWPI_POW_PADPAD-1.0MM"))
    )
    (comp (ref "P52")
      (value "CROWPI_POW_PADPAD-1.0MM")
      (footprint "eagle-import:CROWPI_POW_PAD-1.0MM")
      (libsource (lib "eagle-import") (part "CROWPI_POW_PADPAD-1.0MM"))
    )
    (comp (ref "P53")
      (value "CROWPI_POW_PADPAD-1.0MM")
      (footprint "eagle-import:CROWPI_POW_PAD-1.0MM")
      (libsource (lib "eagle-import") (part "CROWPI_POW_PADPAD-1.0MM"))
    )
    (comp (ref "P54")
      (value "CROWPI_POW_PADPAD-1.0MM")
      (footprint "eagle-import:CROWPI_POW_PAD-1.0MM")
      (libsource (lib "eagle-import") (part "CROWPI_POW_PADPAD-1.0MM"))
    )
    (comp (ref "P55")
      (value "CROWPI_POW_PADPAD-1.0MM")
      (footprint "eagle-import:CROWPI_POW_PAD-1.0MM")
      (libsource (lib "eagle-import") (part "CROWPI_POW_PADPAD-1.0MM"))
    )
    (comp (ref "P56")
      (value "CROWPI_POW_PADPAD-1.0MM")
      (footprint "eagle-import:CROWPI_POW_PAD-1.0MM")
      (libsource (lib "eagle-import") (part "CROWPI_POW_PADPAD-1.0MM"))
    )
    (comp (ref "P57")
      (value "CROWPI_POW_PADPAD-1.0MM")
      (footprint "eagle-import:CROWPI_POW_PAD-1.0MM")
      (libsource (lib "eagle-import") (part "CROWPI_POW_PADPAD-1.0MM"))
    )
    (comp (ref "P58")
      (value "CROWPI_POW_PADPAD-1.0MM")
      (footprint "eagle-import:CROWPI_POW_PAD-1.0MM")
      (libsource (lib "eagle-import") (part "CROWPI_POW_PADPAD-1.0MM"))
    )
    (comp (ref "P59")
      (value "CROWPI_POW_PADPAD-1.0MM")
      (footprint "eagle-import:CROWPI_POW_PAD-1.0MM")
      (libsource (lib "eagle-import") (part "CROWPI_POW_PADPAD-1.0MM"))
    )
    (comp (ref "P60")
      (value "CROWPI_POW_PADPAD-1.0MM")
      (footprint "eagle-import:CROWPI_POW_PAD-1.0MM")
      (libsource (lib "eagle-import") (part "CROWPI_POW_PADPAD-1.0MM"))
    )
    (comp (ref "P61")
      (value "CROWPI_POW_PADPAD-1.0MM")
      (footprint "eagle-import:CROWPI_POW_PAD-1.0MM")
      (libsource (lib "eagle-import") (part "CROWPI_POW_PADPAD-1.0MM"))
    )
    (comp (ref "P62")
      (value "CROWPI_POW_PADPAD-1.0MM")
      (footprint "eagle-import:CROWPI_POW_PAD-1.0MM")
      (libsource (lib "eagle-import") (part "CROWPI_POW_PADPAD-1.0MM"))
    )
    (comp (ref "Q1")
      (value "HXY2102EI")
      (footprint "eagle-import:SOT-323_W")
      (libsource (lib "eagle-import") (part "HXY2102EI"))
    )
    (comp (ref "Q2")
      (value "HXY2102EI")
      (footprint "eagle-import:SOT-323_W")
      (libsource (lib "eagle-import") (part "HXY2102EI"))
    )
    (comp (ref "Q19")
      (value "PMOS-3401-4A")
      (footprint "eagle-import:SOT-23")
      (libsource (lib "eagle-import") (part "P-MOS-SOT23"))
    )
    (comp (ref "R1")
      (value "10K")
      (footprint "eagle-import:DISCRETE_R0603")
      (libsource (lib "eagle-import") (part "Lora_RA-08H_Dev_DISCRETE_R-0603"))
    )
    (comp (ref "R2")
      (value "1K")
      (footprint "eagle-import:DISCRETE_R0603")
      (libsource (lib "eagle-import") (part "Lora_RA-08H_Dev_DISCRETE_R-0603"))
    )
    (comp (ref "R3")
      (value "4.7K")
      (footprint "eagle-import:DISCRETE_R0603")
      (libsource (lib "eagle-import") (part "Crowtail-_LED-V2.0-20190615-01_DISCRETE_R-0603"))
    )
    (comp (ref "R4")
      (value "3R")
      (footprint "eagle-import:DISCRETE_R0603")
      (libsource (lib "eagle-import") (part "Lora_RA-08H_Dev_DISCRETE_R-0603"))
    )
    (comp (ref "R5")
      (value "0R")
      (footprint "eagle-import:DISCRETE_R0603")
      (libsource (lib "eagle-import") (part "Lora_RA-08H_Dev_DISCRETE_R-0603"))
    )
    (comp (ref "R6")
      (value "1K")
      (footprint "eagle-import:DISCRETE_R0603")
      (libsource (lib "eagle-import") (part "Lora_RA-08H_Dev_DISCRETE_R-0603"))
    )
    (comp (ref "R7")
      (value "10K")
      (footprint "eagle-import:DISCRETE_R0603")
      (libsource (lib "eagle-import") (part "Lora_RA-08H_Dev_DISCRETE_R-0603"))
    )
    (comp (ref "R8")
      (value "10K/NC")
      (footprint "eagle-import:DISCRETE_R0603")
      (libsource (lib "eagle-import") (part "DISCRETE_R-0603"))
    )
    (comp (ref "R9")
      (value "0R 5%")
      (footprint "eagle-import:DISCRETE_R0603")
      (libsource (lib "eagle-import") (part "Lora_RA-08H_Dev_DISCRETE_R-0603"))
    )
    (comp (ref "R10")
      (value "22R")
      (footprint "eagle-import:DISCRETE_R0603")
      (libsource (lib "eagle-import") (part "Lora_RA-08H_Dev_DISCRETE_R-0603"))
    )
    (comp (ref "R11")
      (value "22R")
      (footprint "eagle-import:DISCRETE_R0603")
      (libsource (lib "eagle-import") (part "Lora_RA-08H_Dev_DISCRETE_R-0603"))
    )
    (comp (ref "R12")
      (value "5.1K")
      (footprint "eagle-import:DISCRETE_R0603")
      (libsource (lib "eagle-import") (part "Lora_RA-08H_Dev_DISCRETE_R-0603"))
    )
    (comp (ref "R13")
      (value "5.1K")
      (footprint "eagle-import:DISCRETE_R0603")
      (libsource (lib "eagle-import") (part "Lora_RA-08H_Dev_DISCRETE_R-0603"))
    )
    (comp (ref "R14")
      (value "10K/NC")
      (footprint "eagle-import:DISCRETE_R0603")
      (libsource (lib "eagle-import") (part "DISCRETE_R-0603"))
    )
    (comp (ref "R15")
      (value "10K")
      (footprint "eagle-import:DISCRETE_R0603")
      (libsource (lib "eagle-import") (part "Crowtail-_LED-V2.0-20190615-01_DISCRETE_R-0603"))
    )
    (comp (ref "R16")
      (value "NC")
      (footprint "eagle-import:DISCRETE_R0603")
      (libsource (lib "eagle-import") (part "Crowtail-_LED-V2.0-20190615-01_DISCRETE_R-0603"))
    )
    (comp (ref "R17")
      (value "10K")
      (footprint "eagle-import:DISCRETE_R0603")
      (libsource (lib "eagle-import") (part "Crowtail-_LED-V2.0-20190615-01_DISCRETE_R-0603"))
    )
    (comp (ref "R18")
      (value "NC")
      (footprint "eagle-import:DISCRETE_R0603")
      (libsource (lib "eagle-import") (part "Crowtail-_LED-V2.0-20190615-01_DISCRETE_R-0603"))
    )
    (comp (ref "R19")
      (value "100K1%")
      (footprint "eagle-import:DISCRETE_R0603")
      (libsource (lib "eagle-import") (part "DISCRETE_R-0603"))
    )
    (comp (ref "R20")
      (value "100K1%")
      (footprint "eagle-import:DISCRETE_R0603")
      (libsource (lib "eagle-import") (part "DISCRETE_R-0603"))
    )
    (comp (ref "R21")
      (value "10K")
      (footprint "eagle-import:DISCRETE_R0603")
      (libsource (lib "eagle-import") (part "Crowtail-_LED-V2.0-20190615-01_DISCRETE_R-0603"))
    )
    (comp (ref "R22")
      (value "NC")
      (footprint "eagle-import:DISCRETE_R0603")
      (libsource (lib "eagle-import") (part "Crowtail-_LED-V2.0-20190615-01_DISCRETE_R-0603"))
    )
    (comp (ref "R23")
      (value "10K/NC")
      (footprint "eagle-import:DISCRETE_R0603")
      (libsource (lib "eagle-import") (part "DISCRETE_R-0603"))
    )
    (comp (ref "R24")
      (value "1K")
      (footprint "eagle-import:DISCRETE_R0603")
      (libsource (lib "eagle-import") (part "Crowtail-_LED-V2.0-20190615-01_DISCRETE_R-0603"))
    )
    (comp (ref "R25")
      (value "1K")
      (footprint "eagle-import:DISCRETE_R0603")
      (libsource (lib "eagle-import") (part "Crowtail-_LED-V2.0-20190615-01_DISCRETE_R-0603"))
    )
    (comp (ref "R26")
      (value "4.7K")
      (footprint "eagle-import:DISCRETE_R0603")
      (libsource (lib "eagle-import") (part "Crowtail-_LED-V2.0-20190615-01_DISCRETE_R-0603"))
    )
    (comp (ref "R27")
      (value "3R")
      (footprint "eagle-import:DISCRETE_R0603")
      (libsource (lib "eagle-import") (part "Crowtail-_LED-V2.0-20190615-01_DISCRETE_R-0603"))
    )
    (comp (ref "R35")
      (value "4.7K")
      (footprint "eagle-import:DISCRETE_R0603")
      (libsource (lib "eagle-import") (part "Lora_RA-08H_Dev_DISCRETE_R-0603"))
    )
    (comp (ref "R36")
      (value "10K")
      (footprint "eagle-import:DISCRETE_R0603")
      (libsource (lib "eagle-import") (part "Crowtail-_LED-V2.0-20190615-01_DISCRETE_R-0603"))
    )
    (comp (ref "R37")
      (value "10K")
      (footprint "eagle-import:DISCRETE_R0603")
      (libsource (lib "eagle-import") (part "Crowtail-_LED-V2.0-20190615-01_DISCRETE_R-0603"))
    )
    (comp (ref "R38")
      (value "10K")
      (footprint "eagle-import:DISCRETE_R0603")
      (libsource (lib "eagle-import") (part "Crowtail-_LED-V2.0-20190615-01_DISCRETE_R-0603"))
    )
    (comp (ref "R39")
      (value "10K")
      (footprint "eagle-import:DISCRETE_R0603")
      (libsource (lib "eagle-import") (part "Crowtail-_LED-V2.0-20190615-01_DISCRETE_R-0603"))
    )
    (comp (ref "R40")
      (value "10K")
      (footprint "eagle-import:DISCRETE_R0603")
      (libsource (lib "eagle-import") (part "Crowtail-_LED-V2.0-20190615-01_DISCRETE_R-0603"))
    )
    (comp (ref "R66")
      (value "10K")
      (footprint "eagle-import:DISCRETE_R0603")
      (libsource (lib "eagle-import") (part "DISCRETE_R-0603"))
    )
    (comp (ref "R68")
      (value "5.1K")
      (footprint "eagle-import:DISCRETE_R0603")
      (libsource (lib "eagle-import") (part "Crowtail-_LED-V2.0-20190615-01_DISCRETE_R-0603"))
    )
    (comp (ref "R69")
      (value "5.1K")
      (footprint "eagle-import:DISCRETE_R0603")
      (libsource (lib "eagle-import") (part "Crowtail-_LED-V2.0-20190615-01_DISCRETE_R-0603"))
    )
    (comp (ref "R70")
      (value "0R")
      (footprint "eagle-import:DISCRETE_R0603")
      (libsource (lib "eagle-import") (part "Crowtail-_LED-V2.0-20190615-01_DISCRETE_R-0603"))
    )
    (comp (ref "R81")
      (value "45.3K 1%")
      (footprint "eagle-import:DISCRETE_R0603")
      (libsource (lib "eagle-import") (part "Lora_RA-08H_Dev_DISCRETE_R-0603"))
    )
    (comp (ref "R82")
      (value "10K 1%")
      (footprint "eagle-import:DISCRETE_R0603")
      (libsource (lib "eagle-import") (part "Lora_RA-08H_Dev_DISCRETE_R-0603"))
    )
    (comp (ref "R83")
      (value "0R")
      (footprint "eagle-import:DISCRETE_R0603")
      (libsource (lib "eagle-import") (part "Crowtail-_LED-V2.0-20190615-01_DISCRETE_R-0603"))
    )
    (comp (ref "R84")
      (value "2K")
      (footprint "eagle-import:DISCRETE_R0603")
      (libsource (lib "eagle-import") (part "DISCRETE_R-0603"))
    )
    (comp (ref "R85")
      (value "4.7K")
      (footprint "eagle-import:DISCRETE_R0603")
      (libsource (lib "eagle-import") (part "Lora_RA-08H_Dev_DISCRETE_R-0603"))
    )
    (comp (ref "R105")
      (value "10K")
      (footprint "eagle-import:DISCRETE_R0603")
      (libsource (lib "eagle-import") (part "DISCRETE_R-0603"))
    )
    (comp (ref "SD1")
      (value "HOLDER-MICROSD-9P")
      (footprint "eagle-import:9P-SMD-W_-RING")
      (libsource (lib "eagle-import") (part "HOLDER-MICROSD-9P"))
    )
    (comp (ref "SW1")
      (value "KEY-6")
      (footprint "eagle-import:KEY-6")
      (libsource (lib "eagle-import") (part "KEY-6"))
    )
    (comp (ref "SW2")
      (value "KEY-6")
      (footprint "eagle-import:KEY-6")
      (libsource (lib "eagle-import") (part "KEY-6"))
    )
    (comp (ref "T1")
      (value "3M-5")
      (footprint "eagle-import:3M-5")
      (libsource (lib "eagle-import") (part "3M-5"))
    )
    (comp (ref "T2")
      (value "3M-5")
      (footprint "eagle-import:3M-5")
      (libsource (lib "eagle-import") (part "3M-5"))
    )
    (comp (ref "T3")
      (value "3M-5")
      (footprint "eagle-import:3M-5")
      (libsource (lib "eagle-import") (part "3M-5"))
    )
    (comp (ref "T4")
      (value "3M-5")
      (footprint "eagle-import:3M-5")
      (libsource (lib "eagle-import") (part "3M-5"))
    )
    (comp (ref "U1")
      (value "RP2040_RP2040")
      (footprint "eagle-import:RP2040_QFN-56")
      (libsource (lib "eagle-import") (part "RP2040_RP2040"))
    )
    (comp (ref "U2")
      (value "SELF_W25Q128JV")
      (footprint "eagle-import:SELF_SOIC-8-208MIL")
      (libsource (lib "eagle-import") (part "SELF_W25Q128JV"))
    )
    (comp (ref "U3")
      (value "XPT2046")
      (footprint "eagle-import:XP2046-SSOP16")
      (libsource (lib "eagle-import") (part "XPT2046"))
    )
    (comp (ref "U5")
      (value "4054A")
      (footprint "eagle-import:SOP23-5")
      (libsource (lib "eagle-import") (part "4054A"))
    )
    (comp (ref "U6")
      (value "HM3416H")
      (footprint "eagle-import:CROWBOT_-V1.0-20220525_A_XBJ_SOT23-5")
      (libsource (lib "eagle-import") (part "CROWBOT_-V1.0-20220525_A_XBJ_HM3420B"))
    )
    (comp (ref "U7")
      (value "CH340X")
      (footprint "eagle-import:MSOP-10_W")
      (libsource (lib "eagle-import") (part "CH340E"))
    )
    (comp (ref "X1")
      (value "12MHZ_SMD3225")
      (footprint "eagle-import:A_XBJ_SMD3225")
      (libsource (lib "eagle-import") (part "A_XBJ_XTAL"))
    )
  )
  (nets
    (net (code "1") (name "+1V1") (class "Default")
      (node (ref "C13") (pin "1") (pinfunction "1_1") (pintype "passive"))
      (node (ref "C14") (pin "1") (pinfunction "1_1") (pintype "passive"))
      (node (ref "C16") (pin "1") (pinfunction "1_1") (pintype "passive"))
      (node (ref "U1") (pin "23") (pinfunction "VDD_1V1_23") (pintype "bidirectional"))
      (node (ref "U1") (pin "45") (pinfunction "LDO_OUT_45") (pintype "bidirectional"))
      (node (ref "U1") (pin "50") (pinfunction "VDD_1V1_50") (pintype "bidirectional"))
    )
    (net (code "2") (name "+3V3") (class "Default")
      (node (ref "C10") (pin "1") (pinfunction "1_1") (pintype "passive"))
      (node (ref "C11") (pin "1") (pinfunction "1_1") (pintype "passive"))
      (node (ref "C12") (pin "1") (pinfunction "1_1") (pintype "passive"))
      (node (ref "C15") (pin "2") (pinfunction "2_2") (pintype "passive"))
      (node (ref "C17") (pin "1") (pinfunction "1_1") (pintype "passive"))
      (node (ref "C18") (pin "2") (pinfunction "2_2") (pintype "passive"))
      (node (ref "C20") (pin "1") (pinfunction "1_1") (pintype "passive"))
      (node (ref "C21") (pin "2") (pinfunction "2_2") (pintype "passive"))
      (node (ref "C28") (pin "2") (pinfunction "2_2") (pintype "passive"))
      (node (ref "C33") (pin "2") (pinfunction "2_2") (pintype "passive"))
      (node (ref "C35") (pin "1") (pinfunction "1_1") (pintype "passive"))
      (node (ref "C42") (pin "2") (pinfunction "2_2") (pintype "passive"))
      (node (ref "C43") (pin "1") (pinfunction "1_1") (pintype "passive"))
      (node (ref "C5") (pin "1") (pinfunction "1_1") (pintype "passive"))
      (node (ref "C6") (pin "1") (pinfunction "1_1") (pintype "passive"))
      (node (ref "C7") (pin "1") (pinfunction "1_1") (pintype "passive"))
      (node (ref "C8") (pin "1") (pinfunction "1_1") (pintype "passive"))
      (node (ref "C9") (pin "1") (pinfunction "1_1") (pintype "passive"))
      (node (ref "J1") (pin "3") (pinfunction "3_3") (pintype "bidirectional"))
      (node (ref "J17") (pin "6") (pinfunction "IOVCC_6") (pintype "bidirectional"))
      (node (ref "J17") (pin "7") (pinfunction "VDD_7") (pintype "bidirectional"))
      (node (ref "J2") (pin "16") (pinfunction "P$16_16") (pintype "bidirectional"))
      (node (ref "J6") (pin "3") (pinfunction "3_3") (pintype "bidirectional"))
      (node (ref "L4") (pin "2") (pinfunction "P$2_2") (pintype "bidirectional"))
      (node (ref "P10") (pin "P$1") (pinfunction "P$1_P$1") (pintype "bidirectional"))
      (node (ref "P13") (pin "P$1") (pinfunction "P$1_P$1") (pintype "bidirectional"))
      (node (ref "P22") (pin "P$1") (pinfunction "P$1_P$1") (pintype "bidirectional"))
      (node (ref "P30") (pin "P$1") (pinfunction "P$1_P$1") (pintype "bidirectional"))
      (node (ref "P43") (pin "P$1") (pinfunction "P$1_P$1") (pintype "bidirectional"))
      (node (ref "R1") (pin "2") (pinfunction "2_2") (pintype "passive"))
      (node (ref "R105") (pin "2") (pinfunction "2_2") (pintype "passive"))
      (node (ref "R15") (pin "2") (pinfunction "2_2") (pintype "passive"))
      (node (ref "R17") (pin "2") (pinfunction "2_2") (pintype "passive"))
      (node (ref "R21") (pin "2") (pinfunction "2_2") (pintype "passive"))
      (node (ref "R23") (pin "1") (pinfunction "1_1") (pintype "passive"))
      (node (ref "R24") (pin "2") (pinfunction "2_2") (pintype "passive"))
      (node (ref "R25") (pin "2") (pinfunction "2_2") (pintype "passive"))
      (node (ref "R26") (pin "2") (pinfunction "2_2") (pintype "passive"))
      (node (ref "R27") (pin "2") (pinfunction "2_2") (pintype "passive"))
      (node (ref "R3") (pin "2") (pinfunction "2_2") (pintype "passive"))
      (node (ref "R35") (pin "2") (pinfunction "2_2") (pintype "passive"))
      (node (ref "R36") (pin "1") (pinfunction "1_1") (pintype "passive"))
      (node (ref "R37") (pin "1") (pinfunction "1_1") (pintype "passive"))
      (node (ref "R38") (pin "1") (pinfunction "1_1") (pintype "passive"))
      (node (ref "R39") (pin "1") (pinfunction "1_1") (pintype "passive"))
      (node (ref "R4") (pin "2") (pinfunction "2_2") (pintype "passive"))
      (node (ref "R40") (pin "1") (pinfunction "1_1") (pintype "passive"))
      (node (ref "R5") (pin "2") (pinfunction "2_2") (pintype "passive"))
      (node (ref "R7") (pin "2") (pinfunction "2_2") (pintype "passive"))
      (node (ref "R81") (pin "1") (pinfunction "1_1") (pintype "passive"))
      (node (ref "R85") (pin "2") (pinfunction "2_2") (pintype "passive"))
      (node (ref "SD1") (pin "4") (pinfunction "VDD_4") (pintype "bidirectional"))
      (node (ref "U1") (pin "1") (pinfunction "VDDIO_1") (pintype "bidirectional"))
      (node (ref "U1") (pin "10") (pinfunction "VDDIO_10") (pintype "bidirectional"))
      (node (ref "U1") (pin "22") (pinfunction "VDDIO_22") (pintype "bidirectional"))
      (node (ref "U1") (pin "33") (pinfunction "VDDIO_33") (pintype "bidirectional"))
      (node (ref "U1") (pin "42") (pinfunction "VDDIO_42") (pintype "bidirectional"))
      (node (ref "U1") (pin "44") (pinfunction "LDO_IN_44") (pintype "bidirectional"))
      (node (ref "U1") (pin "48") (pinfunction "USB_VDD_48") (pintype "bidirectional"))
      (node (ref "U1") (pin "49") (pinfunction "VDDIO_49") (pintype "bidirectional"))
      (node (ref "U2") (pin "8") (pinfunction "VCC_8") (pintype "bidirectional"))
      (node (ref "U3") (pin "1") (pinfunction "VCC_1") (pintype "bidirectional"))
      (node (ref "U3") (pin "10") (pinfunction "IOVDD_10") (pintype "bidirectional"))
      (node (ref "U3") (pin "9") (pinfunction "VREF_9") (pintype "bidirectional"))
      (node (ref "U7") (pin "10") (pinfunction "V3_10") (pintype "bidirectional"))
      (node (ref "U7") (pin "7") (pinfunction "VCC_7") (pintype "bidirectional"))
    )
    (net (code "3") (name "+5V_UART0") (class "Default")
      (node (ref "D4") (pin "1") (pinfunction "1_1") (pintype "bidirectional"))
      (node (ref "D8") (pin "1") (pinfunction "1_1") (pintype "bidirectional"))
      (node (ref "J15") (pin "A4") (pinfunction "VBUS_A4") (pintype "bidirectional"))
      (node (ref "J15") (pin "A9") (pinfunction "VBUS_A9") (pintype "bidirectional"))
      (node (ref "J15") (pin "B4") (pinfunction "VBUS_B4") (pintype "bidirectional"))
      (node (ref "J15") (pin "B9") (pinfunction "VBUS_B9") (pintype "bidirectional"))
      (node (ref "P26") (pin "P$1") (pinfunction "P$1_P$1") (pintype "bidirectional"))
    )
    (net (code "4") (name "+5V_USB") (class "Default")
      (node (ref "D5") (pin "1") (pinfunction "1_1") (pintype "bidirectional"))
      (node (ref "D6") (pin "1") (pinfunction "1_1") (pintype "bidirectional"))
      (node (ref "J14") (pin "A4") (pinfunction "VBUS_A4") (pintype "bidirectional"))
      (node (ref "J14") (pin "A9") (pinfunction "VBUS_A9") (pintype "bidirectional"))
      (node (ref "J14") (pin "B4") (pinfunction "VBUS_B4") (pintype "bidirectional"))
      (node (ref "J14") (pin "B9") (pinfunction "VBUS_B9") (pintype "bidirectional"))
      (node (ref "P2") (pin "P$1") (pinfunction "P$1_P$1") (pintype "bidirectional"))
    )
    (net (code "5") (name "/CHG_LED") (class "Default")
      (node (ref "D15") (pin "-") (pinfunction "-_-") (pintype "passive"))
      (node (ref "U5") (pin "1") (pinfunction "GHRG_1") (pintype "bidirectional"))
    )
    (net (code "6") (name "/D+") (class "Default")
      (node (ref "J14") (pin "A6") (pinfunction "DP1_A6") (pintype "bidirectional"))
      (node (ref "J14") (pin "B6") (pinfunction "DP2_B6") (pintype "bidirectional"))
      (node (ref "R11") (pin "1") (pinfunction "1_1") (pintype "passive"))
    )
    (net (code "7") (name "/D-") (class "Default")
      (node (ref "J14") (pin "A7") (pinfunction "DN1_A7") (pintype "bidirectional"))
      (node (ref "J14") (pin "B7") (pinfunction "DN2_B7") (pintype "bidirectional"))
      (node (ref "R10") (pin "1") (pinfunction "1_1") (pintype "passive"))
    )
    (net (code "8") (name "/LED-A") (class "Default")
      (node (ref "J17") (pin "33") (pinfunction "LEDA_33") (pintype "bidirectional"))
      (node (ref "P40") (pin "P$1") (pinfunction "P$1_P$1") (pintype "bidirectional"))
      (node (ref "R27") (pin "1") (pinfunction "1_1") (pintype "passive"))
    )
    (net (code "9") (name "/VBAT_IN") (class "Default")
      (node (ref "C22") (pin "2") (pinfunction "2_2") (pintype "bidirectional"))
      (node (ref "C23") (pin "1") (pinfunction "1_1") (pintype "passive"))
      (node (ref "D4") (pin "2") (pinfunction "2_2") (pintype "bidirectional"))
      (node (ref "D5") (pin "2") (pinfunction "2_2") (pintype "bidirectional"))
      (node (ref "Q19") (pin "1") (pinfunction "G_1") (pintype "bidirectional"))
      (node (ref "R66") (pin "2") (pinfunction "2_2") (pintype "passive"))
      (node (ref "U5") (pin "4") (pinfunction "VCC_4") (pintype "bidirectional"))
    )
    (net (code "10") (name "/VIN") (class "Default")
      (node (ref "C31") (pin "2") (pinfunction "2_2") (pintype "passive"))
      (node (ref "C32") (pin "1") (pinfunction "1_1") (pintype "passive"))
      (node (ref "D2") (pin "-") (pinfunction "2_-") (pintype "bidirectional"))
      (node (ref "D6") (pin "2") (pinfunction "2_2") (pintype "bidirectional"))
      (node (ref "D8") (pin "2") (pinfunction "2_2") (pintype "bidirectional"))
      (node (ref "Q19") (pin "2") (pinfunction "S_2") (pintype "bidirectional"))
      (node (ref "U6") (pin "1") (pinfunction "EN_1") (pintype "bidirectional"))
      (node (ref "U6") (pin "4") (pinfunction "VIN_4") (pintype "bidirectional"))
    )
    (net (code "11") (name "AVDD") (class "Default")
      (node (ref "C3") (pin "1") (pinfunction "1_1") (pintype "passive"))
      (node (ref "R5") (pin "1") (pinfunction "1_1") (pintype "passive"))
      (node (ref "U1") (pin "43") (pinfunction "ADC_VDD_43") (pintype "bidirectional"))
    )
    (net (code "12") (name "BAT+") (class "Default")
      (node (ref "C19") (pin "2") (pinfunction "2_2") (pintype "passive"))
      (node (ref "D2") (pin "+") (pinfunction "1_+") (pintype "bidirectional"))
      (node (ref "J16") (pin "P$1") (pinfunction "P$1_P$1") (pintype "bidirectional"))
      (node (ref "P7") (pin "P$1") (pinfunction "P$1_P$1") (pintype "bidirectional"))
      (node (ref "Q19") (pin "3") (pinfunction "D_3") (pintype "bidirectional"))
      (node (ref "R20") (pin "1") (pinfunction "1_1") (pintype "passive"))
      (node (ref "U5") (pin "3") (pinfunction "BAT_3") (pintype "bidirectional"))
    )
    (net (code "13") (name "BOOT") (class "Default")
      (node (ref "R6") (pin "2") (pinfunction "2_2") (pintype "passive"))
      (node (ref "SW2") (pin "2") (pinfunction "2_2") (pintype "bidirectional"))
    )
    (net (code "14") (name "GND") (class "Default")
      (node (ref "C1") (pin "2") (pinfunction "2_2") (pintype "passive"))
      (node (ref "C10") (pin "2") (pinfunction "2_2") (pintype "passive"))
      (node (ref "C11") (pin "2") (pinfunction "2_2") (pintype "passive"))
      (node (ref "C12") (pin "2") (pinfunction "2_2") (pintype "passive"))
      (node (ref "C13") (pin "2") (pinfunction "2_2") (pintype "passive"))
      (node (ref "C14") (pin "2") (pinfunction "2_2") (pintype "passive"))
      (node (ref "C15") (pin "1") (pinfunction "1_1") (pintype "passive"))
      (node (ref "C16") (pin "2") (pinfunction "2_2") (pintype "passive"))
      (node (ref "C17") (pin "2") (pinfunction "2_2") (pintype "passive"))
      (node (ref "C18") (pin "1") (pinfunction "1_1") (pintype "passive"))
      (node (ref "C19") (pin "1") (pinfunction "1_1") (pintype "passive"))
      (node (ref "C2") (pin "1") (pinfunction "1_1") (pintype "passive"))
      (node (ref "C20") (pin "2") (pinfunction "2_2") (pintype "passive"))
      (node (ref "C21") (pin "1") (pinfunction "1_1") (pintype "passive"))
      (node (ref "C22") (pin "1") (pinfunction "1_1") (pintype "bidirectional"))
      (node (ref "C23") (pin "2") (pinfunction "2_2") (pintype "passive"))
      (node (ref "C28") (pin "1") (pinfunction "1_1") (pintype "passive"))
      (node (ref "C3") (pin "2") (pinfunction "2_2") (pintype "passive"))
      (node (ref "C30") (pin "1") (pinfunction "1_1") (pintype "passive"))
      (node (ref "C31") (pin "1") (pinfunction "1_1") (pintype "passive"))
      (node (ref "C32") (pin "2") (pinfunction "2_2") (pintype "passive"))
      (node (ref "C33") (pin "1") (pinfunction "1_1") (pintype "passive"))
      (node (ref "C35") (pin "2") (pinfunction "2_2") (pintype "passive"))
      (node (ref "C38") (pin "1") (pinfunction "1_1") (pintype "passive"))
      (node (ref "C39") (pin "1") (pinfunction "1_1") (pintype "passive"))
      (node (ref "C4") (pin "2") (pinfunction "2_2") (pintype "passive"))
      (node (ref "C40") (pin "1") (pinfunction "1_1") (pintype "passive"))
      (node (ref "C42") (pin "1") (pinfunction "1_1") (pintype "passive"))
      (node (ref "C43") (pin "2") (pinfunction "2_2") (pintype "passive"))
      (node (ref "C5") (pin "2") (pinfunction "2_2") (pintype "passive"))
      (node (ref "C6") (pin "2") (pinfunction "2_2") (pintype "passive"))
      (node (ref "C7") (pin "2") (pinfunction "2_2") (pintype "passive"))
      (node (ref "C8") (pin "2") (pinfunction "2_2") (pintype "passive"))
      (node (ref "C9") (pin "2") (pinfunction "2_2") (pintype "passive"))
      (node (ref "D3") (pin "-") (pinfunction "-_-") (pintype "passive"))
      (node (ref "J1") (pin "4") (pinfunction "4_4") (pintype "bidirectional"))
      (node (ref "J1") (pin "SS1") (pinfunction "SS1_SS1") (pintype "bidirectional"))
      (node (ref "J1") (pin "SS2") (pinfunction "SS2_SS2") (pintype "bidirectional"))
      (node (ref "J14") (pin "A1") (pinfunction "GND_A1") (pintype "bidirectional"))
      (node (ref "J14") (pin "A12") (pinfunction "GND_A12") (pintype "bidirectional"))
      (node (ref "J14") (pin "B1") (pinfunction "GND_B1") (pintype "bidirectional"))
      (node (ref "J14") (pin "B12") (pinfunction "GND_B12") (pintype "bidirectional"))
      (node (ref "J14") (pin "P$6") (pinfunction "P$17_P$6") (pintype "bidirectional"))
      (node (ref "J14") (pin "P$7") (pinfunction "P$18_P$7") (pintype "bidirectional"))
      (node (ref "J14") (pin "P$8") (pinfunction "P$19_P$8") (pintype "bidirectional"))
      (node (ref "J14") (pin "P$9") (pinfunction "P$20_P$9") (pintype "bidirectional"))
      (node (ref "J15") (pin "A1") (pinfunction "GND_A1") (pintype "bidirectional"))
      (node (ref "J15") (pin "A12") (pinfunction "GND_A12") (pintype "bidirectional"))
      (node (ref "J15") (pin "B1") (pinfunction "GND_B1") (pintype "bidirectional"))
      (node (ref "J15") (pin "B12") (pinfunction "GND_B12") (pintype "bidirectional"))
      (node (ref "J15") (pin "P$6") (pinfunction "P$17_P$6") (pintype "bidirectional"))
      (node (ref "J15") (pin "P$7") (pinfunction "P$18_P$7") (pintype "bidirectional"))
      (node (ref "J15") (pin "P$8") (pinfunction "P$19_P$8") (pintype "bidirectional"))
      (node (ref "J15") (pin "P$9") (pinfunction "P$20_P$9") (pintype "bidirectional"))
      (node (ref "J16") (pin "P$2") (pinfunction "P$2_P$2") (pintype "bidirectional"))
      (node (ref "J16") (pin "P$3") (pinfunction "P$3_P$3") (pintype "bidirectional"))
      (node (ref "J16") (pin "P$4") (pinfunction "P$4_P$4") (pintype "bidirectional"))
      (node (ref "J17") (pin "16") (pinfunction "GND2_16") (pintype "bidirectional"))
      (node (ref "J17") (pin "37") (pinfunction "GND3_37") (pintype "bidirectional"))
      (node (ref "J17") (pin "5") (pinfunction "GND1_5") (pintype "bidirectional"))
      (node (ref "J2") (pin "15") (pinfunction "P$15_15") (pintype "bidirectional"))
      (node (ref "J6") (pin "4") (pinfunction "4_4") (pintype "bidirectional"))
      (node (ref "J6") (pin "SS1") (pinfunction "SS1_SS1") (pintype "bidirectional"))
      (node (ref "J6") (pin "SS2") (pinfunction "SS2_SS2") (pintype "bidirectional"))
      (node (ref "P1") (pin "P$1") (pinfunction "P$1_P$1") (pintype "bidirectional"))
      (node (ref "P14") (pin "P$1") (pinfunction "P$1_P$1") (pintype "bidirectional"))
      (node (ref "P21") (pin "P$1") (pinfunction "P$1_P$1") (pintype "bidirectional"))
      (node (ref "P25") (pin "P$1") (pinfunction "P$1_P$1") (pintype "bidirectional"))
      (node (ref "P29") (pin "P$1") (pinfunction "P$1_P$1") (pintype "bidirectional"))
      (node (ref "P42") (pin "P$1") (pinfunction "P$1_P$1") (pintype "bidirectional"))
      (node (ref "P59") (pin "P$1") (pinfunction "P$1_P$1") (pintype "bidirectional"))
      (node (ref "P6") (pin "P$1") (pinfunction "P$1_P$1") (pintype "bidirectional"))
      (node (ref "P9") (pin "P$1") (pinfunction "P$1_P$1") (pintype "bidirectional"))
      (node (ref "Q1") (pin "2") (pinfunction "S_2") (pintype "bidirectional"))
      (node (ref "Q2") (pin "2") (pinfunction "S_2") (pintype "bidirectional"))
      (node (ref "R12") (pin "2") (pinfunction "2_2") (pintype "passive"))
      (node (ref "R13") (pin "1") (pinfunction "1_1") (pintype "passive"))
      (node (ref "R14") (pin "1") (pinfunction "1_1") (pintype "passive"))
      (node (ref "R16") (pin "1") (pinfunction "1_1") (pintype "passive"))
      (node (ref "R18") (pin "1") (pinfunction "1_1") (pintype "passive"))
      (node (ref "R19") (pin "2") (pinfunction "2_2") (pintype "passive"))
      (node (ref "R22") (pin "1") (pinfunction "1_1") (pintype "passive"))
      (node (ref "R66") (pin "1") (pinfunction "1_1") (pintype "passive"))
      (node (ref "R68") (pin "2") (pinfunction "2_2") (pintype "passive"))
      (node (ref "R69") (pin "1") (pinfunction "1_1") (pintype "passive"))
      (node (ref "R8") (pin "1") (pinfunction "1_1") (pintype "passive"))
      (node (ref "R82") (pin "1") (pinfunction "1_1") (pintype "passive"))
      (node (ref "R84") (pin "2") (pinfunction "2_2") (pintype "passive"))
      (node (ref "SD1") (pin "6") (pinfunction "VSS_6") (pintype "bidirectional"))
      (node (ref "SD1") (pin "G1") (pinfunction "G1_G1") (pintype "bidirectional"))
      (node (ref "SD1") (pin "G2") (pinfunction "G2_G2") (pintype "bidirectional"))
      (node (ref "SD1") (pin "G3") (pinfunction "G3_G3") (pintype "bidirectional"))
      (node (ref "SD1") (pin "G4") (pinfunction "G4_G4") (pintype "bidirectional"))
      (node (ref "SW1") (pin "1") (pinfunction "1_1") (pintype "bidirectional"))
      (node (ref "SW2") (pin "1") (pinfunction "1_1") (pintype "bidirectional"))
      (node (ref "T1") (pin "1") (pinfunction "P$1_1") (pintype "bidirectional"))
      (node (ref "T2") (pin "1") (pinfunction "P$1_1") (pintype "bidirectional"))
      (node (ref "T3") (pin "1") (pinfunction "P$1_1") (pintype "bidirectional"))
      (node (ref "T4") (pin "1") (pinfunction "P$1_1") (pintype "bidirectional"))
      (node (ref "U1") (pin "19") (pinfunction "TESTEN_19") (pintype "bidirectional"))
      (node (ref "U1") (pin "EPAD") (pinfunction "GND_EPAD") (pintype "bidirectional"))
      (node (ref "U2") (pin "4") (pinfunction "GND_4") (pintype "bidirectional"))
      (node (ref "U3") (pin "6") (pinfunction "GND_6") (pintype "bidirectional"))
      (node (ref "U5") (pin "2") (pinfunction "GND_2") (pintype "bidirectional"))
      (node (ref "U6") (pin "2") (pinfunction "GND_2") (pintype "bidirectional"))
      (node (ref "U7") (pin "3") (pinfunction "GND_3") (pintype "bidirectional"))
      (node (ref "X1") (pin "2") (pinfunction "GND_2") (pintype "bidirectional"))
      (node (ref "X1") (pin "4") (pinfunction "GND_4") (pintype "bidirectional"))
    )
    (net (code "15") (name "GP0{slash}UART0_TX") (class "Default")
      (node (ref "J2") (pin "1") (pinfunction "P$1_1") (pintype "bidirectional"))
      (node (ref "P8") (pin "P$1") (pinfunction "P$1_P$1") (pintype "bidirectional"))
      (node (ref "R70") (pin "2") (pinfunction "2_2") (pintype "passive"))
      (node (ref "U1") (pin "2") (pinfunction "GPIO0_2") (pintype "bidirectional"))
    )
    (net (code "16") (name "GP1{slash}UART0_RX") (class "Default")
      (node (ref "J2") (pin "2") (pinfunction "P$2_2") (pintype "bidirectional"))
      (node (ref "P17") (pin "P$1") (pinfunction "P$1_P$1") (pintype "bidirectional"))
      (node (ref "R83") (pin "2") (pinfunction "2_2") (pintype "passive"))
      (node (ref "U1") (pin "3") (pinfunction "GPIO1_3") (pintype "bidirectional"))
    )
    (net (code "17") (name "GP2{slash}I2C1_SDA") (class "Default")
      (node (ref "J2") (pin "3") (pinfunction "P$3_3") (pintype "bidirectional"))
      (node (ref "P18") (pin "P$1") (pinfunction "P$1_P$1") (pintype "bidirectional"))
      (node (ref "U1") (pin "4") (pinfunction "GPIO2_4") (pintype "bidirectional"))
    )
    (net (code "18") (name "GP3{slash}I2C1_SCL") (class "Default")
      (node (ref "J2") (pin "4") (pinfunction "P$4_4") (pintype "bidirectional"))
      (node (ref "P19") (pin "P$1") (pinfunction "P$1_P$1") (pintype "bidirectional"))
      (node (ref "U1") (pin "5") (pinfunction "GPIO3_5") (pintype "bidirectional"))
    )
    (net (code "19") (name "GP4{slash}UART1_TX") (class "Default")
      (node (ref "J1") (pin "2") (pinfunction "2_2") (pintype "bidirectional"))
      (node (ref "J2") (pin "5") (pinfunction "P$5_5") (pintype "bidirectional"))
      (node (ref "P20") (pin "P$1") (pinfunction "P$1_P$1") (pintype "bidirectional"))
      (node (ref "P23") (pin "P$1") (pinfunction "P$1_P$1") (pintype "bidirectional"))
      (node (ref "U1") (pin "6") (pinfunction "GPIO4_6") (pintype "bidirectional"))
    )
    (net (code "20") (name "GP5{slash}UART1_RX") (class "Default")
      (node (ref "J1") (pin "1") (pinfunction "1_1") (pintype "bidirectional"))
      (node (ref "J2") (pin "6") (pinfunction "P$6_6") (pintype "bidirectional"))
      (node (ref "P24") (pin "P$1") (pinfunction "P$1_P$1") (pintype "bidirectional"))
      (node (ref "P50") (pin "P$1") (pinfunction "P$1_P$1") (pintype "bidirectional"))
      (node (ref "U1") (pin "7") (pinfunction "GPIO5_7") (pintype "bidirectional"))
    )
    (net (code "21") (name "GP6*I2C1_SDA") (class "Default")
      (node (ref "J2") (pin "7") (pinfunction "P$7_7") (pintype "bidirectional"))
      (node (ref "P51") (pin "P$1") (pinfunction "P$1_P$1") (pintype "bidirectional"))
      (node (ref "U1") (pin "8") (pinfunction "GPIO6_8") (pintype "bidirectional"))
    )
    (net (code "22") (name "GP7*I2C1_SCL") (class "Default")
      (node (ref "J2") (pin "8") (pinfunction "P$8_8") (pintype "bidirectional"))
      (node (ref "P52") (pin "P$1") (pinfunction "P$1_P$1") (pintype "bidirectional"))
      (node (ref "U1") (pin "9") (pinfunction "GPIO7_9") (pintype "bidirectional"))
    )
    (net (code "23") (name "GP8{slash}LCD_DC") (class "Default")
      (node (ref "J17") (pin "10") (pinfunction "RS_10") (pintype "bidirectional"))
      (node (ref "P34") (pin "P$1") (pinfunction "P$1_P$1") (pintype "bidirectional"))
      (node (ref "U1") (pin "11") (pinfunction "GPIO8_11") (pintype "bidirectional"))
    )
    (net (code "24") (name "GP9{slash}LCD_CS{slash}SPI_CS0") (class "Default")
      (node (ref "J17") (pin "9") (pinfunction "CS_9") (pintype "bidirectional"))
      (node (ref "P35") (pin "P$1") (pinfunction "P$1_P$1") (pintype "bidirectional"))
      (node (ref "U1") (pin "12") (pinfunction "GPIO9_12") (pintype "bidirectional"))
    )
    (net (code "25") (name "GP10{slash}SPI_CLK{slash}LCD_CLK{slash}TP_CLK{slash}SD_CLK") (class "Default")
      (node (ref "J17") (pin "11") (pinfunction "WR_11") (pintype "bidirectional"))
      (node (ref "P32") (pin "P$1") (pinfunction "P$1_P$1") (pintype "bidirectional"))
      (node (ref "P45") (pin "P$1") (pinfunction "P$1_P$1") (pintype "bidirectional"))
      (node (ref "R25") (pin "1") (pinfunction "1_1") (pintype "passive"))
      (node (ref "SD1") (pin "5") (pinfunction "SCLK_5") (pintype "bidirectional"))
      (node (ref "U1") (pin "13") (pinfunction "GPIO10_13") (pintype "bidirectional"))
      (node (ref "U3") (pin "16") (pinfunction "DCLK_16") (pintype "bidirectional"))
    )
    (net (code "26") (name "GP11{slash}SPI_MOSI{slash}LCD_SDI{slash}TP_SDI{slash}SD_SDI") (class "Default")
      (node (ref "J17") (pin "13") (pinfunction "SDA_13") (pintype "bidirectional"))
      (node (ref "P36") (pin "P$1") (pinfunction "P$1_P$1") (pintype "bidirectional"))
      (node (ref "P44") (pin "P$1") (pinfunction "P$1_P$1") (pintype "bidirectional"))
      (node (ref "R24") (pin "1") (pinfunction "1_1") (pintype "passive"))
      (node (ref "R39") (pin "2") (pinfunction "2_2") (pintype "passive"))
      (node (ref "SD1") (pin "3") (pinfunction "DI_3") (pintype "bidirectional"))
      (node (ref "U1") (pin "14") (pinfunction "GPIO11_14") (pintype "bidirectional"))
      (node (ref "U3") (pin "14") (pinfunction "DIN_14") (pintype "bidirectional"))
    )
    (net (code "27") (name "GP12{slash}SPI_MISO{slash}LCD_SDO{slash}TP_SDO{slash}SD_SDO") (class "Default")
      (node (ref "P46") (pin "P$1") (pinfunction "P$1_P$1") (pintype "bidirectional"))
      (node (ref "R40") (pin "2") (pinfunction "2_2") (pintype "passive"))
      (node (ref "SD1") (pin "7") (pinfunction "DO_7") (pintype "bidirectional"))
      (node (ref "U1") (pin "15") (pinfunction "GPIO12_15") (pintype "bidirectional"))
      (node (ref "U3") (pin "12") (pinfunction "DOUT_12") (pintype "bidirectional"))
    )
    (net (code "28") (name "GP13{slash}LCD_BL") (class "Default")
      (node (ref "U1") (pin "16") (pinfunction "GPIO13_16") (pintype "bidirectional"))
    )
    (net (code "29") (name "GP14{slash}BUZZER") (class "Default")
      (node (ref "Q2") (pin "1") (pinfunction "G_1") (pintype "bidirectional"))
      (node (ref "R14") (pin "2") (pinfunction "2_2") (pintype "passive"))
      (node (ref "U1") (pin "17") (pinfunction "GPIO14_17") (pintype "bidirectional"))
    )
    (net (code "30") (name "GP15{slash}LCD_RST") (class "Default")
      (node (ref "J17") (pin "15") (pinfunction "REST_15") (pintype "bidirectional"))
      (node (ref "P5") (pin "P$1") (pinfunction "P$1_P$1") (pintype "bidirectional"))
      (node (ref "U1") (pin "18") (pinfunction "GPIO15_18") (pintype "bidirectional"))
    )
    (net (code "31") (name "GP16{slash}TP_CS{slash}SPI_CS1") (class "Default")
      (node (ref "U1") (pin "27") (pinfunction "GPIO16_27") (pintype "bidirectional"))
      (node (ref "U3") (pin "15") (pinfunction "CS_15") (pintype "bidirectional"))
    )
    (net (code "32") (name "GP17{slash}TP_IRQ") (class "Default")
      (node (ref "R105") (pin "1") (pinfunction "1_1") (pintype "passive"))
      (node (ref "U1") (pin "28") (pinfunction "GPIO17_28") (pintype "bidirectional"))
      (node (ref "U3") (pin "11") (pinfunction "PENIRQ_11") (pintype "bidirectional"))
    )
    (net (code "33") (name "GP18{slash}LCD_BL_PWM") (class "Default")
      (node (ref "Q1") (pin "1") (pinfunction "G_1") (pintype "bidirectional"))
      (node (ref "R8") (pin "2") (pinfunction "2_2") (pintype "passive"))
      (node (ref "U1") (pin "29") (pinfunction "GPIO18_29") (pintype "bidirectional"))
    )
    (net (code "34") (name "GP19*") (class "Default")
      (node (ref "J2") (pin "9") (pinfunction "P$9_9") (pintype "bidirectional"))
      (node (ref "P53") (pin "P$1") (pinfunction "P$1_P$1") (pintype "bidirectional"))
      (node (ref "U1") (pin "30") (pinfunction "GPIO19_30") (pintype "bidirectional"))
    )
    (net (code "35") (name "GP20{slash}I2C0_SDA") (class "Default")
      (node (ref "J2") (pin "10") (pinfunction "P$10_10") (pintype "bidirectional"))
      (node (ref "J6") (pin "2") (pinfunction "2_2") (pintype "bidirectional"))
      (node (ref "P15") (pin "P$1") (pinfunction "P$1_P$1") (pintype "bidirectional"))
      (node (ref "P54") (pin "P$1") (pinfunction "P$1_P$1") (pintype "bidirectional"))
      (node (ref "R3") (pin "1") (pinfunction "1_1") (pintype "passive"))
      (node (ref "U1") (pin "31") (pinfunction "GPIO20_31") (pintype "bidirectional"))
    )
    (net (code "36") (name "GP21{slash}I2C0_SCL") (class "Default")
      (node (ref "J2") (pin "11") (pinfunction "P$11_11") (pintype "bidirectional"))
      (node (ref "J6") (pin "1") (pinfunction "1_1") (pintype "bidirectional"))
      (node (ref "P16") (pin "P$1") (pinfunction "P$1_P$1") (pintype "bidirectional"))
      (node (ref "P55") (pin "P$1") (pinfunction "P$1_P$1") (pintype "bidirectional"))
      (node (ref "R26") (pin "1") (pinfunction "1_1") (pintype "passive"))
      (node (ref "U1") (pin "32") (pinfunction "GPIO21_32") (pintype "bidirectional"))
    )
    (net (code "37") (name "GP22{slash}SD_CS{slash}SPI_CS2") (class "Default")
      (node (ref "P47") (pin "P$1") (pinfunction "P$1_P$1") (pintype "bidirectional"))
      (node (ref "R36") (pin "2") (pinfunction "2_2") (pintype "passive"))
      (node (ref "SD1") (pin "2") (pinfunction "CS_2") (pintype "bidirectional"))
      (node (ref "U1") (pin "34") (pinfunction "GPIO22_34") (pintype "bidirectional"))
    )
    (net (code "38") (name "GP23*") (class "Default")
      (node (ref "U1") (pin "35") (pinfunction "GPIO23_35") (pintype "bidirectional"))
    )
    (net (code "39") (name "GP24*") (class "Default")
      (node (ref "U1") (pin "36") (pinfunction "GPIO24_36") (pintype "bidirectional"))
    )
    (net (code "40") (name "GP25{slash}LED") (class "Default")
      (node (ref "U1") (pin "37") (pinfunction "GPIO25_37") (pintype "bidirectional"))
    )
    (net (code "41") (name "GP26*ADC0*I2C1_SDA") (class "Default")
      (node (ref "J2") (pin "12") (pinfunction "P$12_12") (pintype "bidirectional"))
      (node (ref "P56") (pin "P$1") (pinfunction "P$1_P$1") (pintype "bidirectional"))
      (node (ref "U1") (pin "38") (pinfunction "GPIO26/ADC0_38") (pintype "bidirectional"))
    )
    (net (code "42") (name "GP27*ADC1*I2C1_SCL") (class "Default")
      (node (ref "J2") (pin "13") (pinfunction "P$13_13") (pintype "bidirectional"))
      (node (ref "P57") (pin "P$1") (pinfunction "P$1_P$1") (pintype "bidirectional"))
      (node (ref "U1") (pin "39") (pinfunction "GPIO27/ADC1_39") (pintype "bidirectional"))
    )
    (net (code "43") (name "GP28*ADC2") (class "Default")
      (node (ref "J2") (pin "14") (pinfunction "P$14_14") (pintype "bidirectional"))
      (node (ref "P58") (pin "P$1") (pinfunction "P$1_P$1") (pintype "bidirectional"))
      (node (ref "U1") (pin "40") (pinfunction "GPIO28/ADC2_40") (pintype "bidirectional"))
    )
    (net (code "44") (name "GP29{slash}BAT+_ADC3") (class "Default")
      (node (ref "R19") (pin "1") (pinfunction "1_1") (pintype "passive"))
      (node (ref "R20") (pin "2") (pinfunction "2_2") (pintype "passive"))
      (node (ref "U1") (pin "41") (pinfunction "GPIO29/ADC3_41") (pintype "bidirectional"))
    )
    (net (code "45") (name "IM0") (class "Default")
      (node (ref "J17") (pin "38") (pinfunction "IM0_38") (pintype "bidirectional"))
      (node (ref "P60") (pin "P$1") (pinfunction "P$1_P$1") (pintype "bidirectional"))
      (node (ref "R15") (pin "1") (pinfunction "1_1") (pintype "passive"))
      (node (ref "R16") (pin "2") (pinfunction "2_2") (pintype "passive"))
    )
    (net (code "46") (name "IM1") (class "Default")
      (node (ref "J17") (pin "39") (pinfunction "IM1_39") (pintype "bidirectional"))
      (node (ref "P61") (pin "P$1") (pinfunction "P$1_P$1") (pintype "bidirectional"))
      (node (ref "R17") (pin "1") (pinfunction "1_1") (pintype "passive"))
      (node (ref "R18") (pin "2") (pinfunction "2_2") (pintype "passive"))
    )
    (net (code "47") (name "IM2") (class "Default")
      (node (ref "J17") (pin "40") (pinfunction "IM2_40") (pintype "bidirectional"))
      (node (ref "P62") (pin "P$1") (pinfunction "P$1_P$1") (pintype "bidirectional"))
      (node (ref "R21") (pin "1") (pinfunction "1_1") (pintype "passive"))
      (node (ref "R22") (pin "2") (pinfunction "2_2") (pintype "passive"))
    )
    (net (code "48") (name "LED-K") (class "Default")
      (node (ref "J17") (pin "34") (pinfunction "LEDK1_34") (pintype "bidirectional"))
      (node (ref "J17") (pin "35") (pinfunction "LEDK2_35") (pintype "bidirectional"))
      (node (ref "J17") (pin "36") (pinfunction "LEDK3_36") (pintype "bidirectional"))
      (node (ref "P41") (pin "P$1") (pinfunction "P$1_P$1") (pintype "bidirectional"))
      (node (ref "R9") (pin "2") (pinfunction "2_2") (pintype "passive"))
    )
    (net (code "49") (name "Net-(B1-+)") (class "Default")
      (node (ref "B1") (pin "1") (pinfunction "+_1") (pintype "bidirectional"))
      (node (ref "D1") (pin "-") (pinfunction "2_-") (pintype "bidirectional"))
      (node (ref "R4") (pin "1") (pinfunction "1_1") (pintype "passive"))
    )
    (net (code "50") (name "Net-(B1--)") (class "Default")
      (node (ref "B1") (pin "2") (pinfunction "-_2") (pintype "bidirectional"))
      (node (ref "D1") (pin "+") (pinfunction "1_+") (pintype "bidirectional"))
      (node (ref "Q2") (pin "3") (pinfunction "D_3") (pintype "bidirectional"))
    )
    (net (code "51") (name "Net-(D3-Pad+)") (class "Default")
      (node (ref "D3") (pin "+") (pinfunction "+_+") (pintype "passive"))
      (node (ref "R35") (pin "1") (pinfunction "1_1") (pintype "passive"))
    )
    (net (code "52") (name "Net-(D15-Pad+)") (class "Default")
      (node (ref "D15") (pin "+") (pinfunction "+_+") (pintype "passive"))
      (node (ref "R85") (pin "1") (pinfunction "1_1") (pintype "passive"))
    )
    (net (code "53") (name "Net-(J14-CC1)") (class "Default")
      (node (ref "J14") (pin "A5") (pinfunction "CC1_A5") (pintype "bidirectional"))
      (node (ref "R13") (pin "2") (pinfunction "2_2") (pintype "passive"))
    )
    (net (code "54") (name "Net-(J14-CC2)") (class "Default")
      (node (ref "J14") (pin "B5") (pinfunction "CC2_B5") (pintype "bidirectional"))
      (node (ref "R12") (pin "1") (pinfunction "1_1") (pintype "passive"))
    )
    (net (code "55") (name "Net-(J15-CC1)") (class "Default")
      (node (ref "J15") (pin "A5") (pinfunction "CC1_A5") (pintype "bidirectional"))
      (node (ref "R69") (pin "2") (pinfunction "2_2") (pintype "passive"))
    )
    (net (code "56") (name "Net-(J15-CC2)") (class "Default")
      (node (ref "J15") (pin "B5") (pinfunction "CC2_B5") (pintype "bidirectional"))
      (node (ref "R68") (pin "1") (pinfunction "1_1") (pintype "passive"))
    )
    (net (code "57") (name "Net-(L4-P$1)") (class "Default")
      (node (ref "L4") (pin "1") (pinfunction "P$1_1") (pintype "bidirectional"))
      (node (ref "U6") (pin "3") (pinfunction "SW_3") (pintype "bidirectional"))
    )
    (net (code "58") (name "Net-(Q1-D)") (class "Default")
      (node (ref "Q1") (pin "3") (pinfunction "D_3") (pintype "bidirectional"))
      (node (ref "R9") (pin "1") (pinfunction "1_1") (pintype "passive"))
    )
    (net (code "59") (name "Net-(SD1-DATA1)") (class "Default")
      (node (ref "R38") (pin "2") (pinfunction "2_2") (pintype "passive"))
      (node (ref "SD1") (pin "8") (pinfunction "DATA1_8") (pintype "bidirectional"))
    )
    (net (code "60") (name "Net-(SD1-DATA2)") (class "Default")
      (node (ref "R37") (pin "2") (pinfunction "2_2") (pintype "passive"))
      (node (ref "SD1") (pin "1") (pinfunction "DATA2_1") (pintype "bidirectional"))
    )
    (net (code "61") (name "Net-(U1-XIN)") (class "Default")
      (node (ref "C1") (pin "1") (pinfunction "1_1") (pintype "passive"))
      (node (ref "U1") (pin "20") (pinfunction "XIN_20") (pintype "bidirectional"))
      (node (ref "X1") (pin "1") (pinfunction "XIN_1") (pintype "bidirectional"))
    )
    (net (code "62") (name "Net-(U1-XOUT)") (class "Default")
      (node (ref "R2") (pin "2") (pinfunction "2_2") (pintype "passive"))
      (node (ref "U1") (pin "21") (pinfunction "XOUT_21") (pintype "bidirectional"))
    )
    (net (code "63") (name "Net-(U3-VBAT)") (class "Default")
      (node (ref "R23") (pin "2") (pinfunction "2_2") (pintype "passive"))
      (node (ref "U3") (pin "7") (pinfunction "VBAT_7") (pintype "bidirectional"))
    )
    (net (code "64") (name "Net-(U5-PROG)") (class "Default")
      (node (ref "R84") (pin "1") (pinfunction "1_1") (pintype "passive"))
      (node (ref "U5") (pin "5") (pinfunction "PROG_5") (pintype "bidirectional"))
    )
    (net (code "65") (name "Net-(U6-FB)") (class "Default")
      (node (ref "R81") (pin "2") (pinfunction "2_2") (pintype "passive"))
      (node (ref "R82") (pin "2") (pinfunction "2_2") (pintype "passive"))
      (node (ref "U6") (pin "5") (pinfunction "FB_5") (pintype "bidirectional"))
    )
    (net (code "66") (name "Net-(U7-RXD)") (class "Default")
      (node (ref "R70") (pin "1") (pinfunction "1_1") (pintype "passive"))
      (node (ref "U7") (pin "9") (pinfunction "RXD_9") (pintype "bidirectional"))
    )
    (net (code "67") (name "Net-(U7-TXD)") (class "Default")
      (node (ref "R83") (pin "1") (pinfunction "1_1") (pintype "passive"))
      (node (ref "U7") (pin "8") (pinfunction "TXD_8") (pintype "bidirectional"))
    )
    (net (code "68") (name "Net-(X1-XOUT)") (class "Default")
      (node (ref "C2") (pin "2") (pinfunction "2_2") (pintype "passive"))
      (node (ref "R2") (pin "1") (pinfunction "1_1") (pintype "passive"))
      (node (ref "X1") (pin "3") (pinfunction "XOUT_3") (pintype "bidirectional"))
    )
    (net (code "69") (name "QSPI_CS") (class "Default")
      (node (ref "R6") (pin "1") (pinfunction "1_1") (pintype "passive"))
      (node (ref "R7") (pin "1") (pinfunction "1_1") (pintype "passive"))
      (node (ref "U1") (pin "56") (pinfunction "QSPI_~{CS}_56") (pintype "bidirectional"))
      (node (ref "U2") (pin "1") (pinfunction "/CS_1") (pintype "bidirectional"))
    )
    (net (code "70") (name "QSPI_D0") (class "Default")
      (node (ref "U1") (pin "53") (pinfunction "QSPI_SD0_53") (pintype "bidirectional"))
      (node (ref "U2") (pin "5") (pinfunction "DI(IO0)_5") (pintype "bidirectional"))
    )
    (net (code "71") (name "QSPI_D1") (class "Default")
      (node (ref "U1") (pin "55") (pinfunction "QSPI_SD1_55") (pintype "bidirectional"))
      (node (ref "U2") (pin "2") (pinfunction "DO(IO1)_2") (pintype "bidirectional"))
    )
    (net (code "72") (name "QSPI_D2") (class "Default")
      (node (ref "U1") (pin "54") (pinfunction "QSPI_SD2_54") (pintype "bidirectional"))
      (node (ref "U2") (pin "3") (pinfunction "/WP(IO2)_3") (pintype "bidirectional"))
    )
    (net (code "73") (name "QSPI_D3") (class "Default")
      (node (ref "U1") (pin "51") (pinfunction "QSPI_SD3_51") (pintype "bidirectional"))
      (node (ref "U2") (pin "7") (pinfunction "/HOLD/RESET(IO3)_7") (pintype "bidirectional"))
    )
    (net (code "74") (name "QSPI_SCK") (class "Default")
      (node (ref "U1") (pin "52") (pinfunction "QSPI_SCLK_52") (pintype "bidirectional"))
      (node (ref "U2") (pin "6") (pinfunction "CLK_6") (pintype "bidirectional"))
    )
    (net (code "75") (name "RESET") (class "Default")
      (node (ref "C4") (pin "1") (pinfunction "1_1") (pintype "passive"))
      (node (ref "P31") (pin "P$1") (pinfunction "P$1_P$1") (pintype "bidirectional"))
      (node (ref "R1") (pin "1") (pinfunction "1_1") (pintype "passive"))
      (node (ref "SW1") (pin "2") (pinfunction "2_2") (pintype "bidirectional"))
      (node (ref "U1") (pin "26") (pinfunction "RUN_26") (pintype "bidirectional"))
    )
    (net (code "76") (name "SWCLK") (class "Default")
      (node (ref "P11") (pin "P$1") (pinfunction "P$1_P$1") (pintype "bidirectional"))
      (node (ref "U1") (pin "24") (pinfunction "SWCLK_24") (pintype "bidirectional"))
    )
    (net (code "77") (name "SWDIO") (class "Default")
      (node (ref "P12") (pin "P$1") (pinfunction "P$1_P$1") (pintype "bidirectional"))
      (node (ref "U1") (pin "25") (pinfunction "SWDIO_25") (pintype "bidirectional"))
    )
    (net (code "78") (name "TP_X+") (class "Default")
      (node (ref "C30") (pin "2") (pinfunction "2_2") (pintype "passive"))
      (node (ref "J17") (pin "1") (pinfunction "XL_1") (pintype "bidirectional"))
      (node (ref "P33") (pin "P$1") (pinfunction "P$1_P$1") (pintype "bidirectional"))
      (node (ref "U3") (pin "2") (pinfunction "XP_2") (pintype "bidirectional"))
    )
    (net (code "79") (name "TP_X-") (class "Default")
      (node (ref "C39") (pin "2") (pinfunction "2_2") (pintype "passive"))
      (node (ref "J17") (pin "3") (pinfunction "XR_3") (pintype "bidirectional"))
      (node (ref "P38") (pin "P$1") (pinfunction "P$1_P$1") (pintype "bidirectional"))
      (node (ref "U3") (pin "4") (pinfunction "XN_4") (pintype "bidirectional"))
    )
    (net (code "80") (name "TP_Y+") (class "Default")
      (node (ref "C38") (pin "2") (pinfunction "2_2") (pintype "passive"))
      (node (ref "J17") (pin "4") (pinfunction "YD_4") (pintype "bidirectional"))
      (node (ref "P39") (pin "P$1") (pinfunction "P$1_P$1") (pintype "bidirectional"))
      (node (ref "U3") (pin "3") (pinfunction "YP_3") (pintype "bidirectional"))
    )
    (net (code "81") (name "TP_Y-") (class "Default")
      (node (ref "C40") (pin "2") (pinfunction "2_2") (pintype "passive"))
      (node (ref "J17") (pin "2") (pinfunction "YU_2") (pintype "bidirectional"))
      (node (ref "P37") (pin "P$1") (pinfunction "P$1_P$1") (pintype "bidirectional"))
      (node (ref "U3") (pin "5") (pinfunction "YN_5") (pintype "bidirectional"))
    )
    (net (code "82") (name "UART_USB_D+") (class "Default")
      (node (ref "J15") (pin "A6") (pinfunction "DP1_A6") (pintype "bidirectional"))
      (node (ref "J15") (pin "B6") (pinfunction "DP2_B6") (pintype "bidirectional"))
      (node (ref "P27") (pin "P$1") (pinfunction "P$1_P$1") (pintype "bidirectional"))
      (node (ref "U7") (pin "1") (pinfunction "D+_1") (pintype "bidirectional"))
    )
    (net (code "83") (name "UART_USB_D-") (class "Default")
      (node (ref "J15") (pin "A7") (pinfunction "DN1_A7") (pintype "bidirectional"))
      (node (ref "J15") (pin "B7") (pinfunction "DN2_B7") (pintype "bidirectional"))
      (node (ref "P28") (pin "P$1") (pinfunction "P$1_P$1") (pintype "bidirectional"))
      (node (ref "U7") (pin "2") (pinfunction "D-_2") (pintype "bidirectional"))
    )
    (net (code "84") (name "USB_D+") (class "Default")
      (node (ref "P3") (pin "P$1") (pinfunction "P$1_P$1") (pintype "bidirectional"))
      (node (ref "R11") (pin "2") (pinfunction "2_2") (pintype "passive"))
      (node (ref "U1") (pin "47") (pinfunction "USB_D+_47") (pintype "bidirectional"))
    )
    (net (code "85") (name "USB_D-") (class "Default")
      (node (ref "P4") (pin "P$1") (pinfunction "P$1_P$1") (pintype "bidirectional"))
      (node (ref "R10") (pin "2") (pinfunction "2_2") (pintype "passive"))
      (node (ref "U1") (pin "46") (pinfunction "USB_D-_46") (pintype "bidirectional"))
    )
    (net (code "86") (name "unconnected-(J14-SBU1-PadA8)") (class "Default")
      (node (ref "J14") (pin "A8") (pinfunction "SBU1_A8") (pintype "bidirectional"))
    )
    (net (code "87") (name "unconnected-(J14-SBU2-PadB8)") (class "Default")
      (node (ref "J14") (pin "B8") (pinfunction "SBU2_B8") (pintype "bidirectional"))
    )
    (net (code "88") (name "unconnected-(J15-SBU1-PadA8)") (class "Default")
      (node (ref "J15") (pin "A8") (pinfunction "SBU1_A8") (pintype "bidirectional"))
    )
    (net (code "89") (name "unconnected-(J15-SBU2-PadB8)") (class "Default")
      (node (ref "J15") (pin "B8") (pinfunction "SBU2_B8") (pintype "bidirectional"))
    )
    (net (code "90") (name "unconnected-(J17-DB0-Pad17)") (class "Default")
      (node (ref "J17") (pin "17") (pinfunction "DB0_17") (pintype "bidirectional"))
    )
    (net (code "91") (name "unconnected-(J17-DB1-Pad18)") (class "Default")
      (node (ref "J17") (pin "18") (pinfunction "DB1_18") (pintype "bidirectional"))
    )
    (net (code "92") (name "unconnected-(J17-DB2-Pad19)") (class "Default")
      (node (ref "J17") (pin "19") (pinfunction "DB2_19") (pintype "bidirectional"))
    )
    (net (code "93") (name "unconnected-(J17-DB3-Pad20)") (class "Default")
      (node (ref "J17") (pin "20") (pinfunction "DB3_20") (pintype "bidirectional"))
    )
    (net (code "94") (name "unconnected-(J17-DB4-Pad21)") (class "Default")
      (node (ref "J17") (pin "21") (pinfunction "DB4_21") (pintype "bidirectional"))
    )
    (net (code "95") (name "unconnected-(J17-DB5-Pad22)") (class "Default")
      (node (ref "J17") (pin "22") (pinfunction "DB5_22") (pintype "bidirectional"))
    )
    (net (code "96") (name "unconnected-(J17-DB6-Pad23)") (class "Default")
      (node (ref "J17") (pin "23") (pinfunction "DB6_23") (pintype "bidirectional"))
    )
    (net (code "97") (name "unconnected-(J17-DB7-Pad24)") (class "Default")
      (node (ref "J17") (pin "24") (pinfunction "DB7_24") (pintype "bidirectional"))
    )
    (net (code "98") (name "unconnected-(J17-DB8-Pad25)") (class "Default")
      (node (ref "J17") (pin "25") (pinfunction "DB8_25") (pintype "bidirectional"))
    )
    (net (code "99") (name "unconnected-(J17-DB9-Pad26)") (class "Default")
      (node (ref "J17") (pin "26") (pinfunction "DB9_26") (pintype "bidirectional"))
    )
    (net (code "100") (name "unconnected-(J17-DB10-Pad27)") (class "Default")
      (node (ref "J17") (pin "27") (pinfunction "DB10_27") (pintype "bidirectional"))
    )
    (net (code "101") (name "unconnected-(J17-DB11-Pad28)") (class "Default")
      (node (ref "J17") (pin "28") (pinfunction "DB11_28") (pintype "bidirectional"))
    )
    (net (code "102") (name "unconnected-(J17-DB12-Pad29)") (class "Default")
      (node (ref "J17") (pin "29") (pinfunction "DB12_29") (pintype "bidirectional"))
    )
    (net (code "103") (name "unconnected-(J17-DB13-Pad30)") (class "Default")
      (node (ref "J17") (pin "30") (pinfunction "DB13_30") (pintype "bidirectional"))
    )
    (net (code "104") (name "unconnected-(J17-DB14-Pad31)") (class "Default")
      (node (ref "J17") (pin "31") (pinfunction "DB14_31") (pintype "bidirectional"))
    )
    (net (code "105") (name "unconnected-(J17-DB15-Pad32)") (class "Default")
      (node (ref "J17") (pin "32") (pinfunction "DB15_32") (pintype "bidirectional"))
    )
    (net (code "106") (name "unconnected-(J17-FMARK-Pad8)") (class "Default")
      (node (ref "J17") (pin "8") (pinfunction "FMARK_8") (pintype "bidirectional"))
    )
    (net (code "107") (name "unconnected-(J17-RD-Pad12)") (class "Default")
      (node (ref "J17") (pin "12") (pinfunction "RD_12") (pintype "bidirectional"))
    )
    (net (code "108") (name "unconnected-(J17-SDO-Pad14)") (class "Default")
      (node (ref "J17") (pin "14") (pinfunction "SDO_14") (pintype "bidirectional"))
    )
    (net (code "109") (name "unconnected-(P48-PadP$1)") (class "Default")
      (node (ref "P48") (pin "P$1") (pinfunction "P$1_P$1") (pintype "bidirectional"))
    )
    (net (code "110") (name "unconnected-(P49-PadP$1)") (class "Default")
      (node (ref "P49") (pin "P$1") (pinfunction "P$1_P$1") (pintype "bidirectional"))
    )
    (net (code "111") (name "unconnected-(SD1-CDN-Pad9)") (class "Default")
      (node (ref "SD1") (pin "9") (pinfunction "CDN_9") (pintype "bidirectional"))
    )
    (net (code "112") (name "unconnected-(U3-BUESY-Pad13)") (class "Default")
      (node (ref "U3") (pin "13") (pinfunction "BUESY_13") (pintype "bidirectional"))
    )
    (net (code "113") (name "unconnected-(U3-IN-Pad8)") (class "Default")
      (node (ref "U3") (pin "8") (pinfunction "IN_8") (pintype "bidirectional"))
    )
    (net (code "114") (name "unconnected-(U7-CTS-Pad5)") (class "Default")
      (node (ref "U7") (pin "5") (pinfunction "CTS_5") (pintype "bidirectional"))
    )
    (net (code "115") (name "unconnected-(U7-RTS-Pad4)") (class "Default")
      (node (ref "U7") (pin "4") (pinfunction "RTS_4") (pintype "bidirectional"))
    )
    (net (code "116") (name "unconnected-(U7-TNOW-Pad6)") (class "Default")
      (node (ref "U7") (pin "6") (pinfunction "TNOW_6") (pintype "bidirectional"))
    )
  )
)
